# The_Extender_PCB.net
KiCad netlist of a schematic drawn in EAGLE
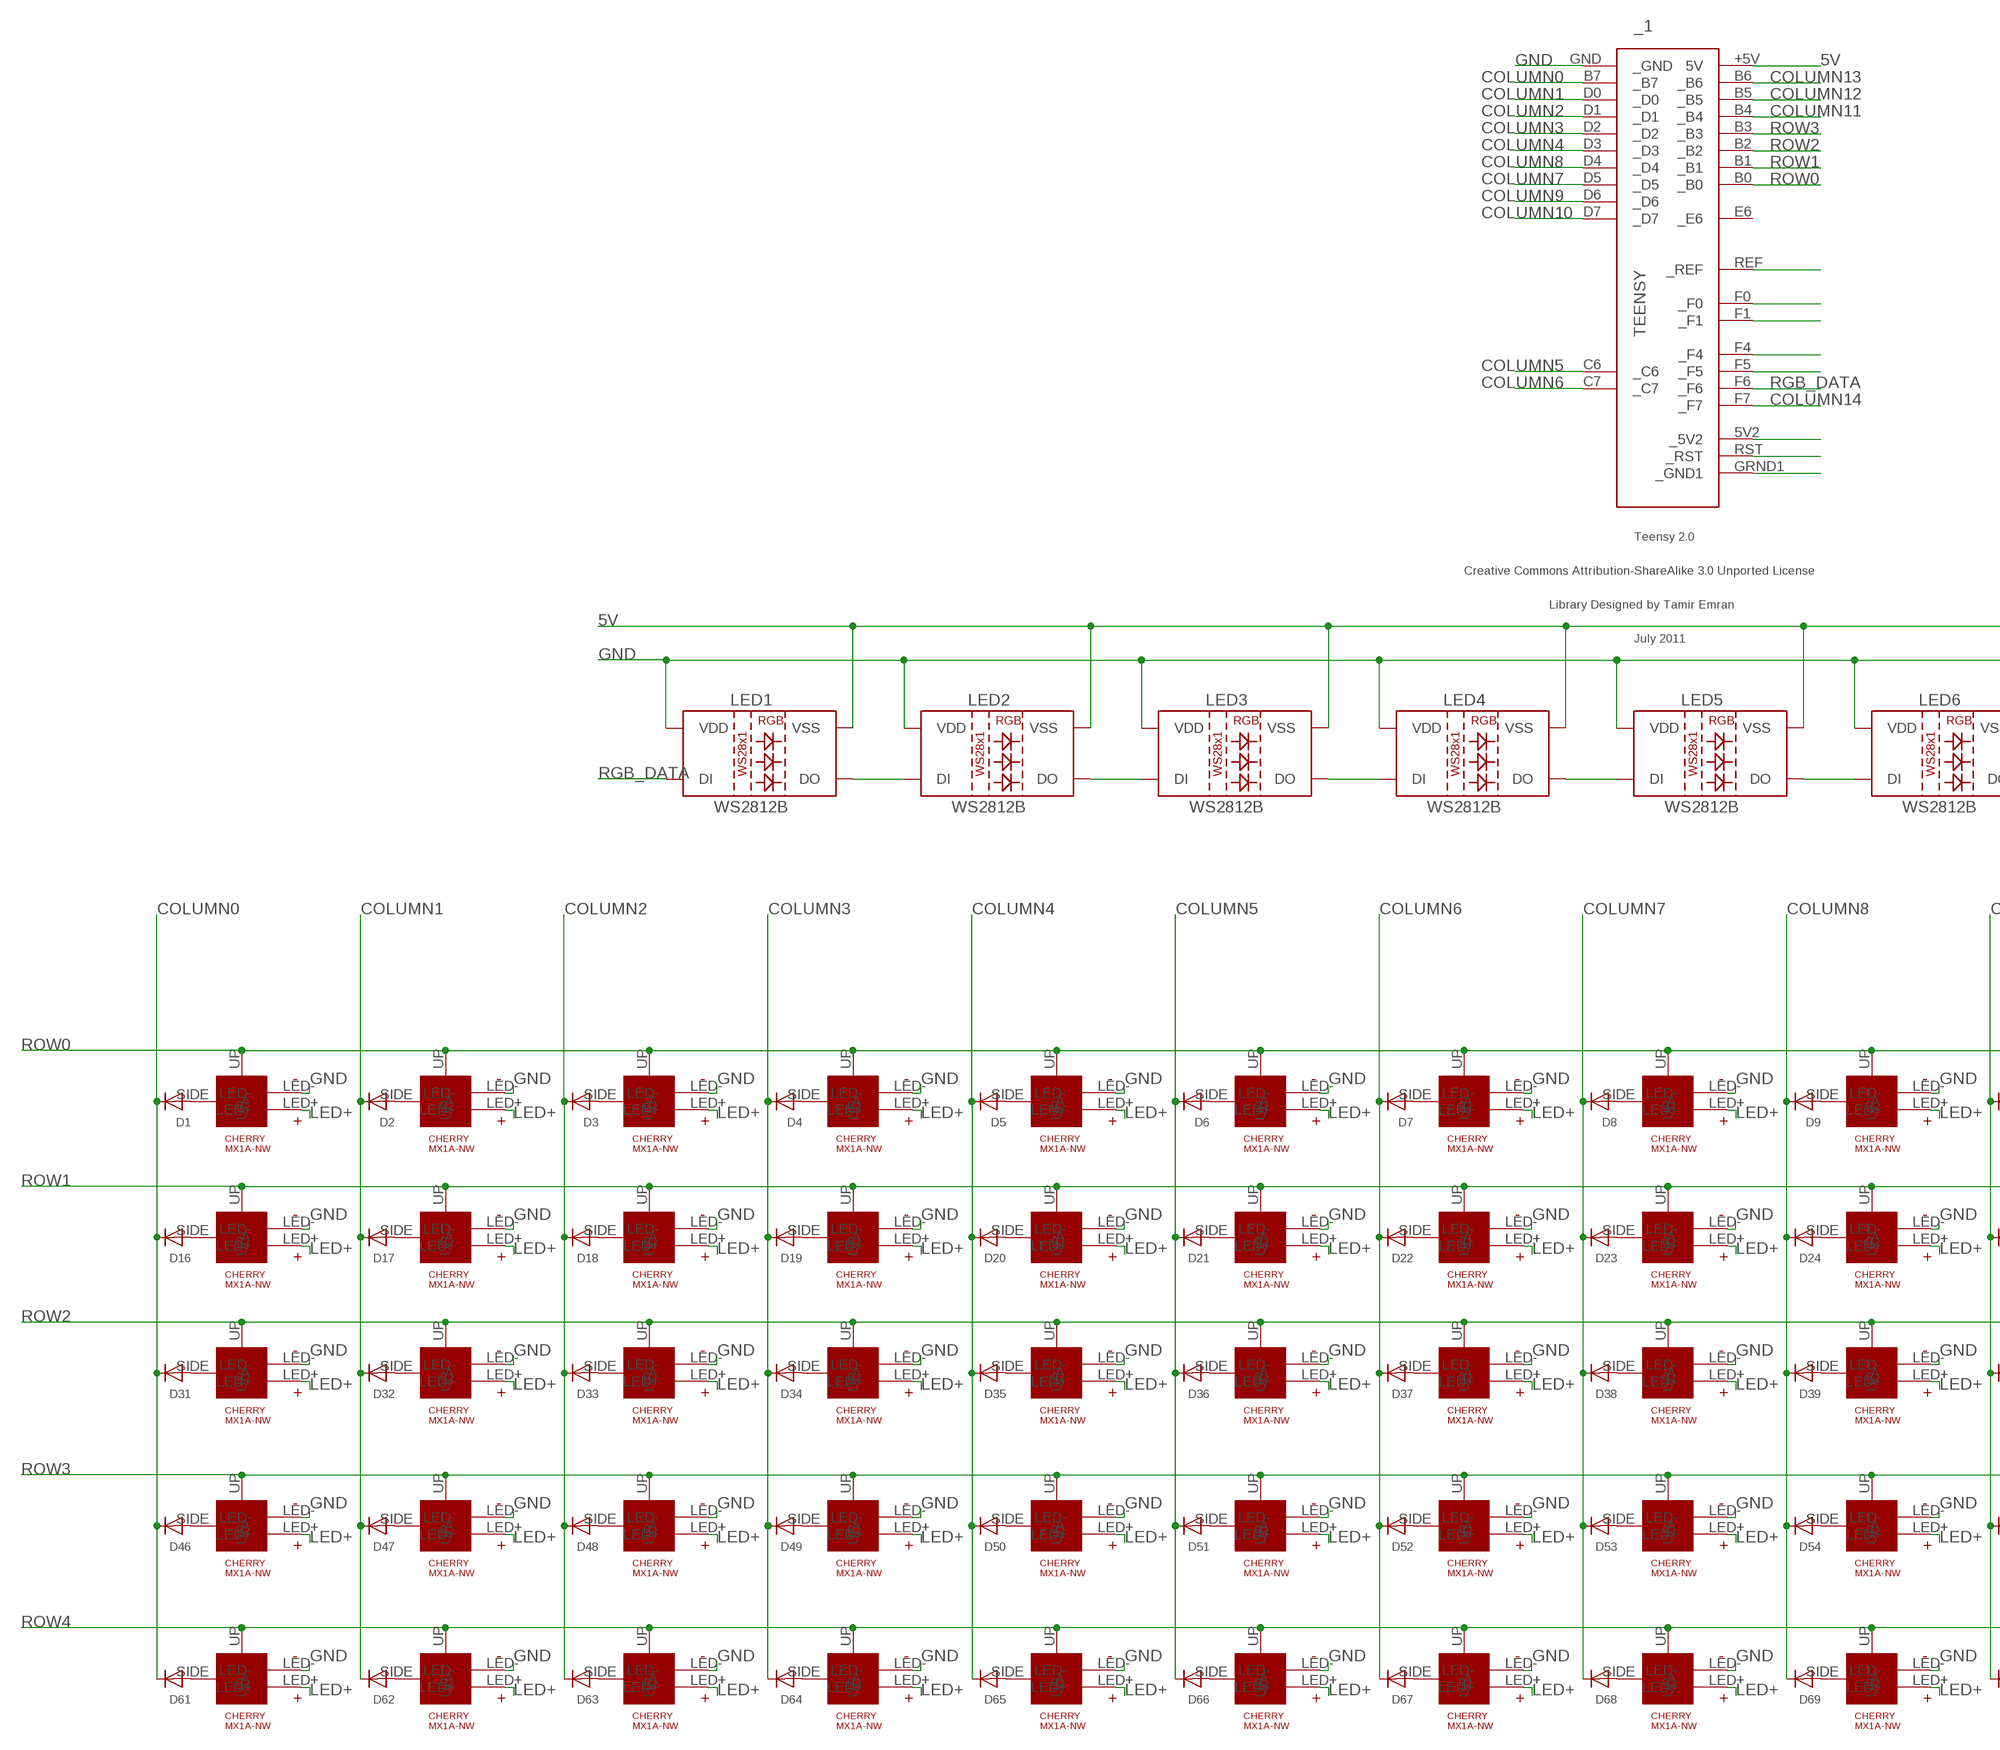
[diagram p0: schematic, sheet 1, part 1 of 2]
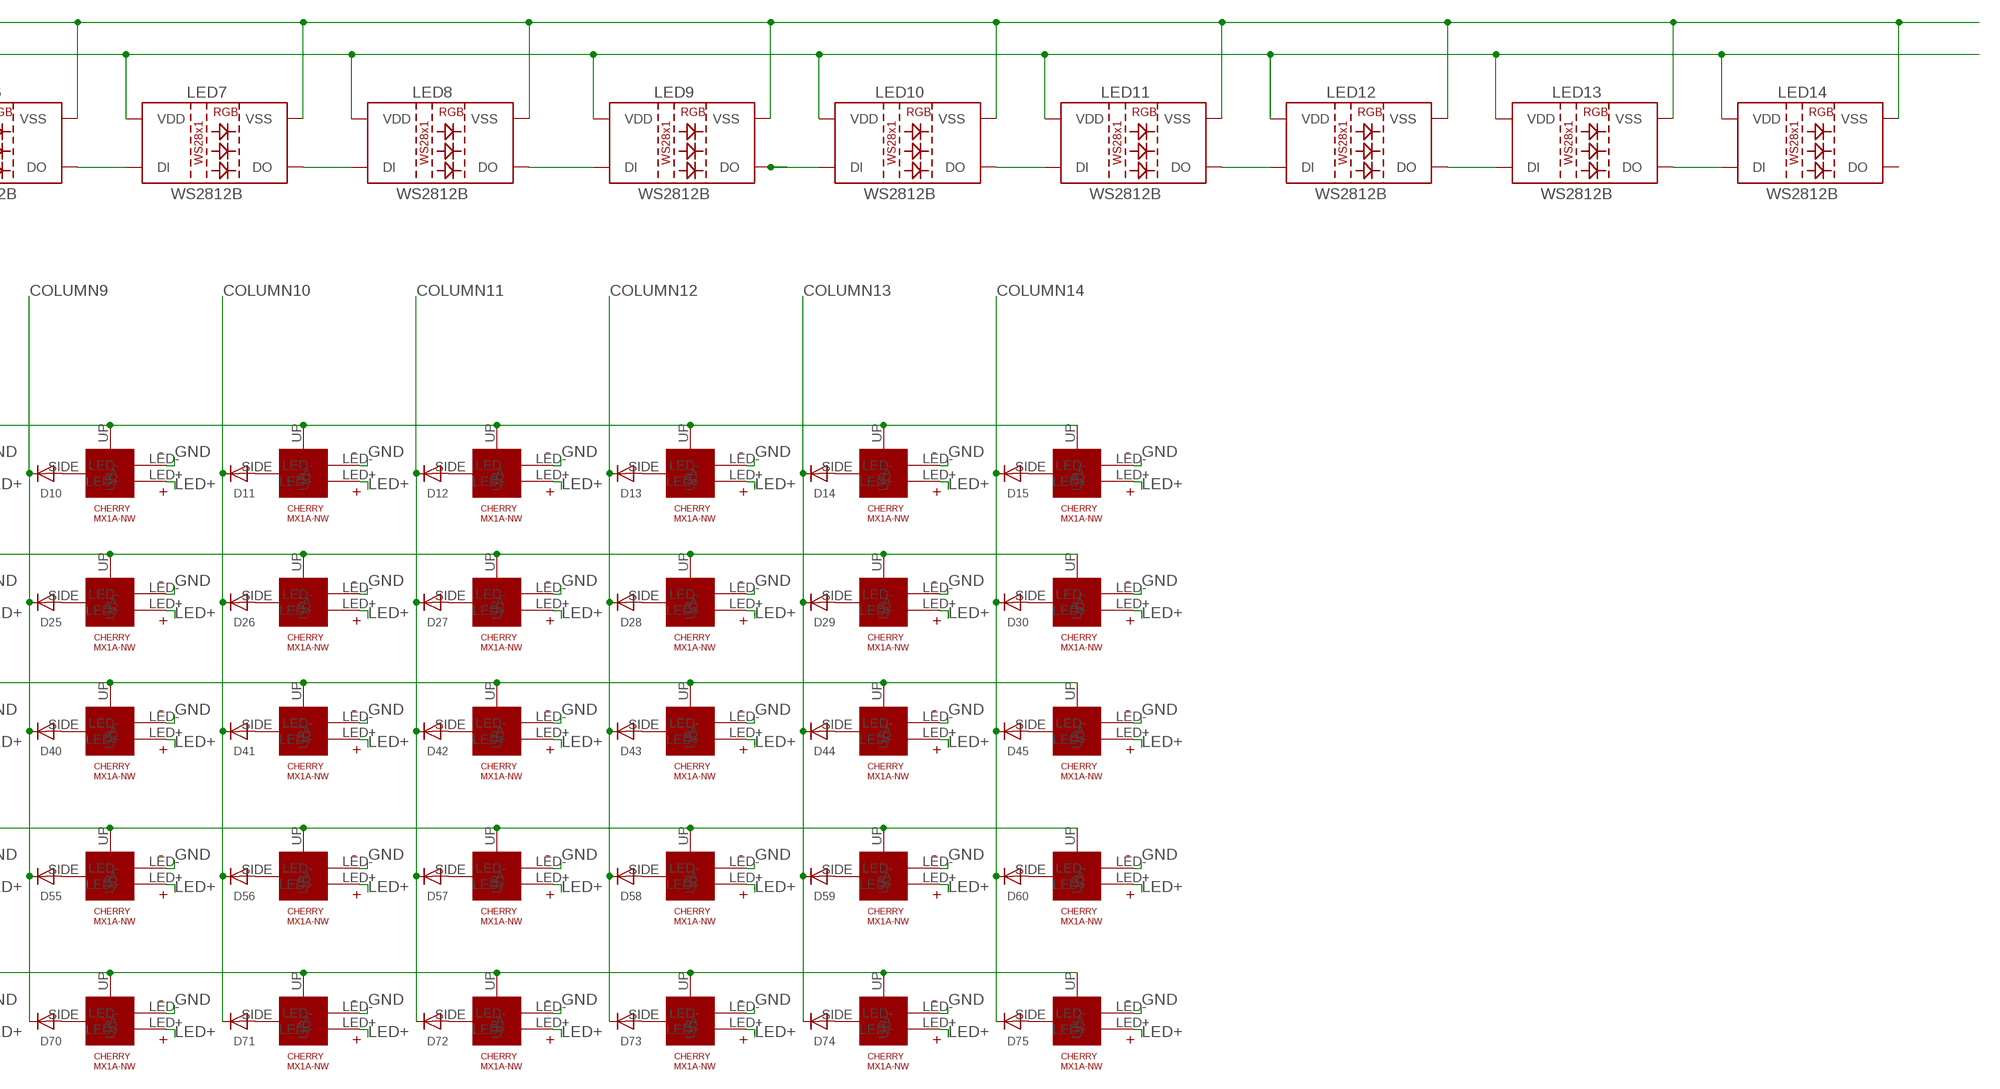
[diagram p1: schematic, sheet 1, part 2 of 2]

(export (version "E")
  (design (tool "Eeschema 10.0.6"))
  (components
    (comp (ref "D1")
      (value "DIODEDO-1N4148")
      (footprint "eagle-import:DO-1N4148")
      (libsource (lib "eagle-import") (part "DIODEDO-1N4148"))
    )
    (comp (ref "D2")
      (value "DIODEDO-1N4148")
      (footprint "eagle-import:DO-1N4148")
      (libsource (lib "eagle-import") (part "DIODEDO-1N4148"))
    )
    (comp (ref "D3")
      (value "DIODEDO-1N4148")
      (footprint "eagle-import:DO-1N4148")
      (libsource (lib "eagle-import") (part "DIODEDO-1N4148"))
    )
    (comp (ref "D4")
      (value "DIODEDO-1N4148")
      (footprint "eagle-import:DO-1N4148")
      (libsource (lib "eagle-import") (part "DIODEDO-1N4148"))
    )
    (comp (ref "D5")
      (value "DIODEDO-1N4148")
      (footprint "eagle-import:DO-1N4148")
      (libsource (lib "eagle-import") (part "DIODEDO-1N4148"))
    )
    (comp (ref "D6")
      (value "DIODEDO-1N4148")
      (footprint "eagle-import:DO-1N4148")
      (libsource (lib "eagle-import") (part "DIODEDO-1N4148"))
    )
    (comp (ref "D7")
      (value "DIODEDO-1N4148")
      (footprint "eagle-import:DO-1N4148")
      (libsource (lib "eagle-import") (part "DIODEDO-1N4148"))
    )
    (comp (ref "D8")
      (value "DIODEDO-1N4148")
      (footprint "eagle-import:DO-1N4148")
      (libsource (lib "eagle-import") (part "DIODEDO-1N4148"))
    )
    (comp (ref "D9")
      (value "DIODEDO-1N4148")
      (footprint "eagle-import:DO-1N4148")
      (libsource (lib "eagle-import") (part "DIODEDO-1N4148"))
    )
    (comp (ref "D10")
      (value "DIODEDO-1N4148")
      (footprint "eagle-import:DO-1N4148")
      (libsource (lib "eagle-import") (part "DIODEDO-1N4148"))
    )
    (comp (ref "D11")
      (value "DIODEDO-1N4148")
      (footprint "eagle-import:DO-1N4148")
      (libsource (lib "eagle-import") (part "DIODEDO-1N4148"))
    )
    (comp (ref "D12")
      (value "DIODEDO-1N4148")
      (footprint "eagle-import:DO-1N4148")
      (libsource (lib "eagle-import") (part "DIODEDO-1N4148"))
    )
    (comp (ref "D13")
      (value "DIODEDO-1N4148")
      (footprint "eagle-import:DO-1N4148")
      (libsource (lib "eagle-import") (part "DIODEDO-1N4148"))
    )
    (comp (ref "D14")
      (value "DIODEDO-1N4148")
      (footprint "eagle-import:DO-1N4148")
      (libsource (lib "eagle-import") (part "DIODEDO-1N4148"))
    )
    (comp (ref "D15")
      (value "DIODEDO-1N4148")
      (footprint "eagle-import:DO-1N4148")
      (libsource (lib "eagle-import") (part "DIODEDO-1N4148"))
    )
    (comp (ref "D16")
      (value "DIODEDO-1N4148")
      (footprint "eagle-import:DO-1N4148")
      (libsource (lib "eagle-import") (part "DIODEDO-1N4148"))
    )
    (comp (ref "D17")
      (value "DIODEDO-1N4148")
      (footprint "eagle-import:DO-1N4148")
      (libsource (lib "eagle-import") (part "DIODEDO-1N4148"))
    )
    (comp (ref "D18")
      (value "DIODEDO-1N4148")
      (footprint "eagle-import:DO-1N4148")
      (libsource (lib "eagle-import") (part "DIODEDO-1N4148"))
    )
    (comp (ref "D19")
      (value "DIODEDO-1N4148")
      (footprint "eagle-import:DO-1N4148")
      (libsource (lib "eagle-import") (part "DIODEDO-1N4148"))
    )
    (comp (ref "D20")
      (value "DIODEDO-1N4148")
      (footprint "eagle-import:DO-1N4148")
      (libsource (lib "eagle-import") (part "DIODEDO-1N4148"))
    )
    (comp (ref "D21")
      (value "DIODEDO-1N4148")
      (footprint "eagle-import:DO-1N4148")
      (libsource (lib "eagle-import") (part "DIODEDO-1N4148"))
    )
    (comp (ref "D22")
      (value "DIODEDO-1N4148")
      (footprint "eagle-import:DO-1N4148")
      (libsource (lib "eagle-import") (part "DIODEDO-1N4148"))
    )
    (comp (ref "D23")
      (value "DIODEDO-1N4148")
      (footprint "eagle-import:DO-1N4148")
      (libsource (lib "eagle-import") (part "DIODEDO-1N4148"))
    )
    (comp (ref "D24")
      (value "DIODEDO-1N4148")
      (footprint "eagle-import:DO-1N4148")
      (libsource (lib "eagle-import") (part "DIODEDO-1N4148"))
    )
    (comp (ref "D25")
      (value "DIODEDO-1N4148")
      (footprint "eagle-import:DO-1N4148")
      (libsource (lib "eagle-import") (part "DIODEDO-1N4148"))
    )
    (comp (ref "D26")
      (value "DIODEDO-1N4148")
      (footprint "eagle-import:DO-1N4148")
      (libsource (lib "eagle-import") (part "DIODEDO-1N4148"))
    )
    (comp (ref "D27")
      (value "DIODEDO-1N4148")
      (footprint "eagle-import:DO-1N4148")
      (libsource (lib "eagle-import") (part "DIODEDO-1N4148"))
    )
    (comp (ref "D28")
      (value "DIODEDO-1N4148")
      (footprint "eagle-import:DO-1N4148")
      (libsource (lib "eagle-import") (part "DIODEDO-1N4148"))
    )
    (comp (ref "D29")
      (value "DIODEDO-1N4148")
      (footprint "eagle-import:DO-1N4148")
      (libsource (lib "eagle-import") (part "DIODEDO-1N4148"))
    )
    (comp (ref "D30")
      (value "DIODEDO-1N4148")
      (footprint "eagle-import:DO-1N4148")
      (libsource (lib "eagle-import") (part "DIODEDO-1N4148"))
    )
    (comp (ref "D31")
      (value "DIODEDO-1N4148")
      (footprint "eagle-import:DO-1N4148")
      (libsource (lib "eagle-import") (part "DIODEDO-1N4148"))
    )
    (comp (ref "D32")
      (value "DIODEDO-1N4148")
      (footprint "eagle-import:DO-1N4148")
      (libsource (lib "eagle-import") (part "DIODEDO-1N4148"))
    )
    (comp (ref "D33")
      (value "DIODEDO-1N4148")
      (footprint "eagle-import:DO-1N4148")
      (libsource (lib "eagle-import") (part "DIODEDO-1N4148"))
    )
    (comp (ref "D34")
      (value "DIODEDO-1N4148")
      (footprint "eagle-import:DO-1N4148")
      (libsource (lib "eagle-import") (part "DIODEDO-1N4148"))
    )
    (comp (ref "D35")
      (value "DIODEDO-1N4148")
      (footprint "eagle-import:DO-1N4148")
      (libsource (lib "eagle-import") (part "DIODEDO-1N4148"))
    )
    (comp (ref "D36")
      (value "DIODEDO-1N4148")
      (footprint "eagle-import:DO-1N4148")
      (libsource (lib "eagle-import") (part "DIODEDO-1N4148"))
    )
    (comp (ref "D37")
      (value "DIODEDO-1N4148")
      (footprint "eagle-import:DO-1N4148")
      (libsource (lib "eagle-import") (part "DIODEDO-1N4148"))
    )
    (comp (ref "D38")
      (value "DIODEDO-1N4148")
      (footprint "eagle-import:DO-1N4148")
      (libsource (lib "eagle-import") (part "DIODEDO-1N4148"))
    )
    (comp (ref "D39")
      (value "DIODEDO-1N4148")
      (footprint "eagle-import:DO-1N4148")
      (libsource (lib "eagle-import") (part "DIODEDO-1N4148"))
    )
    (comp (ref "D40")
      (value "DIODEDO-1N4148")
      (footprint "eagle-import:DO-1N4148")
      (libsource (lib "eagle-import") (part "DIODEDO-1N4148"))
    )
    (comp (ref "D41")
      (value "DIODEDO-1N4148")
      (footprint "eagle-import:DO-1N4148")
      (libsource (lib "eagle-import") (part "DIODEDO-1N4148"))
    )
    (comp (ref "D42")
      (value "DIODEDO-1N4148")
      (footprint "eagle-import:DO-1N4148")
      (libsource (lib "eagle-import") (part "DIODEDO-1N4148"))
    )
    (comp (ref "D43")
      (value "DIODEDO-1N4148")
      (footprint "eagle-import:DO-1N4148")
      (libsource (lib "eagle-import") (part "DIODEDO-1N4148"))
    )
    (comp (ref "D44")
      (value "DIODEDO-1N4148")
      (footprint "eagle-import:DO-1N4148")
      (libsource (lib "eagle-import") (part "DIODEDO-1N4148"))
    )
    (comp (ref "D45")
      (value "DIODEDO-1N4148")
      (footprint "eagle-import:DO-1N4148")
      (libsource (lib "eagle-import") (part "DIODEDO-1N4148"))
    )
    (comp (ref "D46")
      (value "DIODEDO-1N4148")
      (footprint "eagle-import:DO-1N4148")
      (libsource (lib "eagle-import") (part "DIODEDO-1N4148"))
    )
    (comp (ref "D47")
      (value "DIODEDO-1N4148")
      (footprint "eagle-import:DO-1N4148")
      (libsource (lib "eagle-import") (part "DIODEDO-1N4148"))
    )
    (comp (ref "D48")
      (value "DIODEDO-1N4148")
      (footprint "eagle-import:DO-1N4148")
      (libsource (lib "eagle-import") (part "DIODEDO-1N4148"))
    )
    (comp (ref "D49")
      (value "DIODEDO-1N4148")
      (footprint "eagle-import:DO-1N4148")
      (libsource (lib "eagle-import") (part "DIODEDO-1N4148"))
    )
    (comp (ref "D50")
      (value "DIODEDO-1N4148")
      (footprint "eagle-import:DO-1N4148")
      (libsource (lib "eagle-import") (part "DIODEDO-1N4148"))
    )
    (comp (ref "D51")
      (value "DIODEDO-1N4148")
      (footprint "eagle-import:DO-1N4148")
      (libsource (lib "eagle-import") (part "DIODEDO-1N4148"))
    )
    (comp (ref "D52")
      (value "DIODEDO-1N4148")
      (footprint "eagle-import:DO-1N4148")
      (libsource (lib "eagle-import") (part "DIODEDO-1N4148"))
    )
    (comp (ref "D53")
      (value "DIODEDO-1N4148")
      (footprint "eagle-import:DO-1N4148")
      (libsource (lib "eagle-import") (part "DIODEDO-1N4148"))
    )
    (comp (ref "D54")
      (value "DIODEDO-1N4148")
      (footprint "eagle-import:DO-1N4148")
      (libsource (lib "eagle-import") (part "DIODEDO-1N4148"))
    )
    (comp (ref "D55")
      (value "DIODEDO-1N4148")
      (footprint "eagle-import:DO-1N4148")
      (libsource (lib "eagle-import") (part "DIODEDO-1N4148"))
    )
    (comp (ref "D56")
      (value "DIODEDO-1N4148")
      (footprint "eagle-import:DO-1N4148")
      (libsource (lib "eagle-import") (part "DIODEDO-1N4148"))
    )
    (comp (ref "D57")
      (value "DIODEDO-1N4148")
      (footprint "eagle-import:DO-1N4148")
      (libsource (lib "eagle-import") (part "DIODEDO-1N4148"))
    )
    (comp (ref "D58")
      (value "DIODEDO-1N4148")
      (footprint "eagle-import:DO-1N4148")
      (libsource (lib "eagle-import") (part "DIODEDO-1N4148"))
    )
    (comp (ref "D59")
      (value "DIODEDO-1N4148")
      (footprint "eagle-import:DO-1N4148")
      (libsource (lib "eagle-import") (part "DIODEDO-1N4148"))
    )
    (comp (ref "D60")
      (value "DIODEDO-1N4148")
      (footprint "eagle-import:DO-1N4148")
      (libsource (lib "eagle-import") (part "DIODEDO-1N4148"))
    )
    (comp (ref "D61")
      (value "DIODEDO-1N4148")
      (footprint "eagle-import:DO-1N4148")
      (libsource (lib "eagle-import") (part "DIODEDO-1N4148"))
    )
    (comp (ref "D62")
      (value "DIODEDO-1N4148")
      (footprint "eagle-import:DO-1N4148")
      (libsource (lib "eagle-import") (part "DIODEDO-1N4148"))
    )
    (comp (ref "D63")
      (value "DIODEDO-1N4148")
      (footprint "eagle-import:DO-1N4148")
      (libsource (lib "eagle-import") (part "DIODEDO-1N4148"))
    )
    (comp (ref "D64")
      (value "DIODEDO-1N4148")
      (footprint "eagle-import:DO-1N4148")
      (libsource (lib "eagle-import") (part "DIODEDO-1N4148"))
    )
    (comp (ref "D65")
      (value "DIODEDO-1N4148")
      (footprint "eagle-import:DO-1N4148")
      (libsource (lib "eagle-import") (part "DIODEDO-1N4148"))
    )
    (comp (ref "D66")
      (value "DIODEDO-1N4148")
      (footprint "eagle-import:DO-1N4148")
      (libsource (lib "eagle-import") (part "DIODEDO-1N4148"))
    )
    (comp (ref "D67")
      (value "DIODEDO-1N4148")
      (footprint "eagle-import:DO-1N4148")
      (libsource (lib "eagle-import") (part "DIODEDO-1N4148"))
    )
    (comp (ref "D68")
      (value "DIODEDO-1N4148")
      (footprint "eagle-import:DO-1N4148")
      (libsource (lib "eagle-import") (part "DIODEDO-1N4148"))
    )
    (comp (ref "D69")
      (value "DIODEDO-1N4148")
      (footprint "eagle-import:DO-1N4148")
      (libsource (lib "eagle-import") (part "DIODEDO-1N4148"))
    )
    (comp (ref "D70")
      (value "DIODEDO-1N4148")
      (footprint "eagle-import:DO-1N4148")
      (libsource (lib "eagle-import") (part "DIODEDO-1N4148"))
    )
    (comp (ref "D71")
      (value "DIODEDO-1N4148")
      (footprint "eagle-import:DO-1N4148")
      (libsource (lib "eagle-import") (part "DIODEDO-1N4148"))
    )
    (comp (ref "D72")
      (value "DIODEDO-1N4148")
      (footprint "eagle-import:DO-1N4148")
      (libsource (lib "eagle-import") (part "DIODEDO-1N4148"))
    )
    (comp (ref "D73")
      (value "DIODEDO-1N4148")
      (footprint "eagle-import:DO-1N4148")
      (libsource (lib "eagle-import") (part "DIODEDO-1N4148"))
    )
    (comp (ref "D74")
      (value "DIODEDO-1N4148")
      (footprint "eagle-import:DO-1N4148")
      (libsource (lib "eagle-import") (part "DIODEDO-1N4148"))
    )
    (comp (ref "D75")
      (value "DIODEDO-1N4148")
      (footprint "eagle-import:DO-1N4148")
      (libsource (lib "eagle-import") (part "DIODEDO-1N4148"))
    )
    (comp (ref "LED1")
      (value "WS2812B")
      (footprint "eagle-import:WS2812B")
      (libsource (lib "eagle-import") (part "WS2812B"))
    )
    (comp (ref "LED2")
      (value "WS2812B")
      (footprint "eagle-import:WS2812B")
      (libsource (lib "eagle-import") (part "WS2812B"))
    )
    (comp (ref "LED3")
      (value "WS2812B")
      (footprint "eagle-import:WS2812B")
      (libsource (lib "eagle-import") (part "WS2812B"))
    )
    (comp (ref "LED4")
      (value "WS2812B")
      (footprint "eagle-import:WS2812B")
      (libsource (lib "eagle-import") (part "WS2812B"))
    )
    (comp (ref "LED5")
      (value "WS2812B")
      (footprint "eagle-import:WS2812B")
      (libsource (lib "eagle-import") (part "WS2812B"))
    )
    (comp (ref "LED6")
      (value "WS2812B")
      (footprint "eagle-import:WS2812B")
      (libsource (lib "eagle-import") (part "WS2812B"))
    )
    (comp (ref "LED7")
      (value "WS2812B")
      (footprint "eagle-import:WS2812B")
      (libsource (lib "eagle-import") (part "WS2812B"))
    )
    (comp (ref "LED8")
      (value "WS2812B")
      (footprint "eagle-import:WS2812B")
      (libsource (lib "eagle-import") (part "WS2812B"))
    )
    (comp (ref "LED9")
      (value "WS2812B")
      (footprint "eagle-import:WS2812B")
      (libsource (lib "eagle-import") (part "WS2812B"))
    )
    (comp (ref "LED10")
      (value "WS2812B")
      (footprint "eagle-import:WS2812B")
      (libsource (lib "eagle-import") (part "WS2812B"))
    )
    (comp (ref "LED11")
      (value "WS2812B")
      (footprint "eagle-import:WS2812B")
      (libsource (lib "eagle-import") (part "WS2812B"))
    )
    (comp (ref "LED12")
      (value "WS2812B")
      (footprint "eagle-import:WS2812B")
      (libsource (lib "eagle-import") (part "WS2812B"))
    )
    (comp (ref "LED13")
      (value "WS2812B")
      (footprint "eagle-import:WS2812B")
      (libsource (lib "eagle-import") (part "WS2812B"))
    )
    (comp (ref "LED14")
      (value "WS2812B")
      (footprint "eagle-import:WS2812B")
      (libsource (lib "eagle-import") (part "WS2812B"))
    )
    (comp (ref "U$1")
      (value "CHERRY-MX1A-E1NW-LED")
      (footprint "eagle-import:CHERRYMX-NN-LED")
      (libsource (lib "eagle-import") (part "CHERRY-MX1A-E1NW-LED"))
    )
    (comp (ref "U$2")
      (value "CHERRY-MX1A-E1NW-LED")
      (footprint "eagle-import:CHERRYMX-NN-LED")
      (libsource (lib "eagle-import") (part "CHERRY-MX1A-E1NW-LED"))
    )
    (comp (ref "U$3")
      (value "CHERRY-MX1A-E1NW-LED")
      (footprint "eagle-import:CHERRYMX-NN-LED")
      (libsource (lib "eagle-import") (part "CHERRY-MX1A-E1NW-LED"))
    )
    (comp (ref "U$4")
      (value "CHERRY-MX1A-E1NW-LED")
      (footprint "eagle-import:CHERRYMX-NN-LED")
      (libsource (lib "eagle-import") (part "CHERRY-MX1A-E1NW-LED"))
    )
    (comp (ref "U$5")
      (value "CHERRY-MX1A-E1NW-LED")
      (footprint "eagle-import:CHERRYMX-NN-LED")
      (libsource (lib "eagle-import") (part "CHERRY-MX1A-E1NW-LED"))
    )
    (comp (ref "U$6")
      (value "CHERRY-MX1A-E1NW-LED")
      (footprint "eagle-import:CHERRYMX-NN-LED")
      (libsource (lib "eagle-import") (part "CHERRY-MX1A-E1NW-LED"))
    )
    (comp (ref "U$7")
      (value "CHERRY-MX1A-E1NW-LED")
      (footprint "eagle-import:CHERRYMX-NN-LED")
      (libsource (lib "eagle-import") (part "CHERRY-MX1A-E1NW-LED"))
    )
    (comp (ref "U$8")
      (value "CHERRY-MX1A-E1NW-LED")
      (footprint "eagle-import:CHERRYMX-NN-LED")
      (libsource (lib "eagle-import") (part "CHERRY-MX1A-E1NW-LED"))
    )
    (comp (ref "U$9")
      (value "CHERRY-MX1A-E1NW-LED")
      (footprint "eagle-import:CHERRYMX-NN-LED")
      (libsource (lib "eagle-import") (part "CHERRY-MX1A-E1NW-LED"))
    )
    (comp (ref "U$10")
      (value "CHERRY-MX1A-E1NW-LED")
      (footprint "eagle-import:CHERRYMX-NN-LED")
      (libsource (lib "eagle-import") (part "CHERRY-MX1A-E1NW-LED"))
    )
    (comp (ref "U$11")
      (value "CHERRY-MX1A-E1NW-LED")
      (footprint "eagle-import:CHERRYMX-NN-LED")
      (libsource (lib "eagle-import") (part "CHERRY-MX1A-E1NW-LED"))
    )
    (comp (ref "U$12")
      (value "CHERRY-MX1A-E1NW-LED")
      (footprint "eagle-import:CHERRYMX-NN-LED")
      (libsource (lib "eagle-import") (part "CHERRY-MX1A-E1NW-LED"))
    )
    (comp (ref "U$13")
      (value "CHERRY-MX1A-E1NW-LED")
      (footprint "eagle-import:CHERRYMX-NN-LED")
      (libsource (lib "eagle-import") (part "CHERRY-MX1A-E1NW-LED"))
    )
    (comp (ref "U$14")
      (value "CHERRY-MX1A-E1NW-LED")
      (footprint "eagle-import:CHERRYMX-NN-LED")
      (libsource (lib "eagle-import") (part "CHERRY-MX1A-E1NW-LED"))
    )
    (comp (ref "U$15")
      (value "CHERRY-MX1A-E1NW-LED")
      (footprint "eagle-import:CHERRYMX-NN-LED")
      (libsource (lib "eagle-import") (part "CHERRY-MX1A-E1NW-LED"))
    )
    (comp (ref "U$16")
      (value "CHERRY-MX1A-E1NW-LED")
      (footprint "eagle-import:CHERRYMX-NN-LED")
      (libsource (lib "eagle-import") (part "CHERRY-MX1A-E1NW-LED"))
    )
    (comp (ref "U$17")
      (value "CHERRY-MX1A-E1NW-LED")
      (footprint "eagle-import:CHERRYMX-NN-LED")
      (libsource (lib "eagle-import") (part "CHERRY-MX1A-E1NW-LED"))
    )
    (comp (ref "U$18")
      (value "CHERRY-MX1A-E1NW-LED")
      (footprint "eagle-import:CHERRYMX-NN-LED")
      (libsource (lib "eagle-import") (part "CHERRY-MX1A-E1NW-LED"))
    )
    (comp (ref "U$19")
      (value "CHERRY-MX1A-E1NW-LED")
      (footprint "eagle-import:CHERRYMX-NN-LED")
      (libsource (lib "eagle-import") (part "CHERRY-MX1A-E1NW-LED"))
    )
    (comp (ref "U$20")
      (value "CHERRY-MX1A-E1NW-LED")
      (footprint "eagle-import:CHERRYMX-NN-LED")
      (libsource (lib "eagle-import") (part "CHERRY-MX1A-E1NW-LED"))
    )
    (comp (ref "U$21")
      (value "CHERRY-MX1A-E1NW-LED")
      (footprint "eagle-import:CHERRYMX-NN-LED")
      (libsource (lib "eagle-import") (part "CHERRY-MX1A-E1NW-LED"))
    )
    (comp (ref "U$22")
      (value "CHERRY-MX1A-E1NW-LED")
      (footprint "eagle-import:CHERRYMX-NN-LED")
      (libsource (lib "eagle-import") (part "CHERRY-MX1A-E1NW-LED"))
    )
    (comp (ref "U$23")
      (value "CHERRY-MX1A-E1NW-LED")
      (footprint "eagle-import:CHERRYMX-NN-LED")
      (libsource (lib "eagle-import") (part "CHERRY-MX1A-E1NW-LED"))
    )
    (comp (ref "U$24")
      (value "CHERRY-MX1A-E1NW-LED")
      (footprint "eagle-import:CHERRYMX-NN-LED")
      (libsource (lib "eagle-import") (part "CHERRY-MX1A-E1NW-LED"))
    )
    (comp (ref "U$25")
      (value "CHERRY-MX1A-E1NW-LED")
      (footprint "eagle-import:CHERRYMX-NN-LED")
      (libsource (lib "eagle-import") (part "CHERRY-MX1A-E1NW-LED"))
    )
    (comp (ref "U$26")
      (value "CHERRY-MX1A-E1NW-LED")
      (footprint "eagle-import:CHERRYMX-NN-LED")
      (libsource (lib "eagle-import") (part "CHERRY-MX1A-E1NW-LED"))
    )
    (comp (ref "U$27")
      (value "CHERRY-MX1A-E1NW-LED")
      (footprint "eagle-import:CHERRYMX-NN-LED")
      (libsource (lib "eagle-import") (part "CHERRY-MX1A-E1NW-LED"))
    )
    (comp (ref "U$28")
      (value "CHERRY-MX1A-E1NW-LED")
      (footprint "eagle-import:CHERRYMX-NN-LED")
      (libsource (lib "eagle-import") (part "CHERRY-MX1A-E1NW-LED"))
    )
    (comp (ref "U$29")
      (value "CHERRY-MX1A-E1NW-LED")
      (footprint "eagle-import:CHERRYMX-NN-LED")
      (libsource (lib "eagle-import") (part "CHERRY-MX1A-E1NW-LED"))
    )
    (comp (ref "U$30")
      (value "CHERRY-MX1A-E1NW-LED")
      (footprint "eagle-import:CHERRYMX-NN-LED")
      (libsource (lib "eagle-import") (part "CHERRY-MX1A-E1NW-LED"))
    )
    (comp (ref "U$31")
      (value "CHERRY-MX1A-E1NW-LED")
      (footprint "eagle-import:CHERRYMX-NN-LED")
      (libsource (lib "eagle-import") (part "CHERRY-MX1A-E1NW-LED"))
    )
    (comp (ref "U$32")
      (value "CHERRY-MX1A-E1NW-LED")
      (footprint "eagle-import:CHERRYMX-NN-LED")
      (libsource (lib "eagle-import") (part "CHERRY-MX1A-E1NW-LED"))
    )
    (comp (ref "U$33")
      (value "CHERRY-MX1A-E1NW-LED")
      (footprint "eagle-import:CHERRYMX-NN-LED")
      (libsource (lib "eagle-import") (part "CHERRY-MX1A-E1NW-LED"))
    )
    (comp (ref "U$34")
      (value "CHERRY-MX1A-E1NW-LED")
      (footprint "eagle-import:CHERRYMX-NN-LED")
      (libsource (lib "eagle-import") (part "CHERRY-MX1A-E1NW-LED"))
    )
    (comp (ref "U$35")
      (value "CHERRY-MX1A-E1NW-LED")
      (footprint "eagle-import:CHERRYMX-NN-LED")
      (libsource (lib "eagle-import") (part "CHERRY-MX1A-E1NW-LED"))
    )
    (comp (ref "U$36")
      (value "CHERRY-MX1A-E1NW-LED")
      (footprint "eagle-import:CHERRYMX-NN-LED")
      (libsource (lib "eagle-import") (part "CHERRY-MX1A-E1NW-LED"))
    )
    (comp (ref "U$37")
      (value "CHERRY-MX1A-E1NW-LED")
      (footprint "eagle-import:CHERRYMX-NN-LED")
      (libsource (lib "eagle-import") (part "CHERRY-MX1A-E1NW-LED"))
    )
    (comp (ref "U$38")
      (value "CHERRY-MX1A-E1NW-LED")
      (footprint "eagle-import:CHERRYMX-NN-LED")
      (libsource (lib "eagle-import") (part "CHERRY-MX1A-E1NW-LED"))
    )
    (comp (ref "U$39")
      (value "CHERRY-MX1A-E1NW-LED")
      (footprint "eagle-import:CHERRYMX-NN-LED")
      (libsource (lib "eagle-import") (part "CHERRY-MX1A-E1NW-LED"))
    )
    (comp (ref "U$40")
      (value "CHERRY-MX1A-E1NW-LED")
      (footprint "eagle-import:CHERRYMX-NN-LED")
      (libsource (lib "eagle-import") (part "CHERRY-MX1A-E1NW-LED"))
    )
    (comp (ref "U$41")
      (value "CHERRY-MX1A-E1NW-LED")
      (footprint "eagle-import:CHERRYMX-NN-LED")
      (libsource (lib "eagle-import") (part "CHERRY-MX1A-E1NW-LED"))
    )
    (comp (ref "U$42")
      (value "CHERRY-MX1A-E1NW-LED")
      (footprint "eagle-import:CHERRYMX-NN-LED")
      (libsource (lib "eagle-import") (part "CHERRY-MX1A-E1NW-LED"))
    )
    (comp (ref "U$43")
      (value "CHERRY-MX1A-E1NW-LED")
      (footprint "eagle-import:CHERRYMX-NN-LED")
      (libsource (lib "eagle-import") (part "CHERRY-MX1A-E1NW-LED"))
    )
    (comp (ref "U$44")
      (value "CHERRY-MX1A-E1NW-LED")
      (footprint "eagle-import:CHERRYMX-NN-LED")
      (libsource (lib "eagle-import") (part "CHERRY-MX1A-E1NW-LED"))
    )
    (comp (ref "U$45")
      (value "CHERRY-MX1A-E1NW-LED")
      (footprint "eagle-import:CHERRYMX-NN-LED")
      (libsource (lib "eagle-import") (part "CHERRY-MX1A-E1NW-LED"))
    )
    (comp (ref "U$46")
      (value "CHERRY-MX1A-E1NW-LED")
      (footprint "eagle-import:CHERRYMX-NN-LED")
      (libsource (lib "eagle-import") (part "CHERRY-MX1A-E1NW-LED"))
    )
    (comp (ref "U$47")
      (value "CHERRY-MX1A-E1NW-LED")
      (footprint "eagle-import:CHERRYMX-NN-LED")
      (libsource (lib "eagle-import") (part "CHERRY-MX1A-E1NW-LED"))
    )
    (comp (ref "U$48")
      (value "CHERRY-MX1A-E1NW-LED")
      (footprint "eagle-import:CHERRYMX-NN-LED")
      (libsource (lib "eagle-import") (part "CHERRY-MX1A-E1NW-LED"))
    )
    (comp (ref "U$49")
      (value "CHERRY-MX1A-E1NW-LED")
      (footprint "eagle-import:CHERRYMX-NN-LED")
      (libsource (lib "eagle-import") (part "CHERRY-MX1A-E1NW-LED"))
    )
    (comp (ref "U$50")
      (value "CHERRY-MX1A-E1NW-LED")
      (footprint "eagle-import:CHERRYMX-NN-LED")
      (libsource (lib "eagle-import") (part "CHERRY-MX1A-E1NW-LED"))
    )
    (comp (ref "U$51")
      (value "CHERRY-MX1A-E1NW-LED")
      (footprint "eagle-import:CHERRYMX-NN-LED")
      (libsource (lib "eagle-import") (part "CHERRY-MX1A-E1NW-LED"))
    )
    (comp (ref "U$52")
      (value "CHERRY-MX1A-E1NW-LED")
      (footprint "eagle-import:CHERRYMX-NN-LED")
      (libsource (lib "eagle-import") (part "CHERRY-MX1A-E1NW-LED"))
    )
    (comp (ref "U$53")
      (value "CHERRY-MX1A-E1NW-LED")
      (footprint "eagle-import:CHERRYMX-NN-LED")
      (libsource (lib "eagle-import") (part "CHERRY-MX1A-E1NW-LED"))
    )
    (comp (ref "U$54")
      (value "CHERRY-MX1A-E1NW-LED")
      (footprint "eagle-import:CHERRYMX-NN-LED")
      (libsource (lib "eagle-import") (part "CHERRY-MX1A-E1NW-LED"))
    )
    (comp (ref "U$55")
      (value "CHERRY-MX1A-E1NW-LED")
      (footprint "eagle-import:CHERRYMX-NN-LED")
      (libsource (lib "eagle-import") (part "CHERRY-MX1A-E1NW-LED"))
    )
    (comp (ref "U$56")
      (value "CHERRY-MX1A-E1NW-LED")
      (footprint "eagle-import:CHERRYMX-NN-LED")
      (libsource (lib "eagle-import") (part "CHERRY-MX1A-E1NW-LED"))
    )
    (comp (ref "U$57")
      (value "CHERRY-MX1A-E1NW-LED")
      (footprint "eagle-import:CHERRYMX-NN-LED")
      (libsource (lib "eagle-import") (part "CHERRY-MX1A-E1NW-LED"))
    )
    (comp (ref "U$58")
      (value "CHERRY-MX1A-E1NW-LED")
      (footprint "eagle-import:CHERRYMX-NN-LED")
      (libsource (lib "eagle-import") (part "CHERRY-MX1A-E1NW-LED"))
    )
    (comp (ref "U$59")
      (value "CHERRY-MX1A-E1NW-LED")
      (footprint "eagle-import:CHERRYMX-NN-LED")
      (libsource (lib "eagle-import") (part "CHERRY-MX1A-E1NW-LED"))
    )
    (comp (ref "U$60")
      (value "CHERRY-MX1A-E1NW-LED")
      (footprint "eagle-import:CHERRYMX-NN-LED")
      (libsource (lib "eagle-import") (part "CHERRY-MX1A-E1NW-LED"))
    )
    (comp (ref "U$61")
      (value "CHERRY-MX1A-E1NW-LED")
      (footprint "eagle-import:CHERRYMX-NN-LED")
      (libsource (lib "eagle-import") (part "CHERRY-MX1A-E1NW-LED"))
    )
    (comp (ref "U$62")
      (value "CHERRY-MX1A-E1NW-LED")
      (footprint "eagle-import:CHERRYMX-NN-LED")
      (libsource (lib "eagle-import") (part "CHERRY-MX1A-E1NW-LED"))
    )
    (comp (ref "U$63")
      (value "CHERRY-MX1A-E1NW-LED")
      (footprint "eagle-import:CHERRYMX-NN-LED")
      (libsource (lib "eagle-import") (part "CHERRY-MX1A-E1NW-LED"))
    )
    (comp (ref "U$64")
      (value "CHERRY-MX1A-E1NW-LED")
      (footprint "eagle-import:CHERRYMX-NN-LED")
      (libsource (lib "eagle-import") (part "CHERRY-MX1A-E1NW-LED"))
    )
    (comp (ref "U$65")
      (value "CHERRY-MX1A-E1NW-LED")
      (footprint "eagle-import:CHERRYMX-NN-LED")
      (libsource (lib "eagle-import") (part "CHERRY-MX1A-E1NW-LED"))
    )
    (comp (ref "U$66")
      (value "CHERRY-MX1A-E1NW-LED")
      (footprint "eagle-import:CHERRYMX-NN-LED")
      (libsource (lib "eagle-import") (part "CHERRY-MX1A-E1NW-LED"))
    )
    (comp (ref "U$67")
      (value "CHERRY-MX1A-E1NW-LED")
      (footprint "eagle-import:CHERRYMX-NN-LED")
      (libsource (lib "eagle-import") (part "CHERRY-MX1A-E1NW-LED"))
    )
    (comp (ref "U$68")
      (value "CHERRY-MX1A-E1NW-LED")
      (footprint "eagle-import:CHERRYMX-NN-LED")
      (libsource (lib "eagle-import") (part "CHERRY-MX1A-E1NW-LED"))
    )
    (comp (ref "U$69")
      (value "CHERRY-MX1A-E1NW-LED")
      (footprint "eagle-import:CHERRYMX-NN-LED")
      (libsource (lib "eagle-import") (part "CHERRY-MX1A-E1NW-LED"))
    )
    (comp (ref "U$70")
      (value "CHERRY-MX1A-E1NW-LED")
      (footprint "eagle-import:CHERRYMX-NN-LED")
      (libsource (lib "eagle-import") (part "CHERRY-MX1A-E1NW-LED"))
    )
    (comp (ref "U$71")
      (value "CHERRY-MX1A-E1NW-LED")
      (footprint "eagle-import:CHERRYMX-NN-LED")
      (libsource (lib "eagle-import") (part "CHERRY-MX1A-E1NW-LED"))
    )
    (comp (ref "U$72")
      (value "CHERRY-MX1A-E1NW-LED")
      (footprint "eagle-import:CHERRYMX-NN-LED")
      (libsource (lib "eagle-import") (part "CHERRY-MX1A-E1NW-LED"))
    )
    (comp (ref "U$73")
      (value "CHERRY-MX1A-E1NW-LED")
      (footprint "eagle-import:CHERRYMX-NN-LED")
      (libsource (lib "eagle-import") (part "CHERRY-MX1A-E1NW-LED"))
    )
    (comp (ref "U$74")
      (value "CHERRY-MX1A-E1NW-LED")
      (footprint "eagle-import:CHERRYMX-NN-LED")
      (libsource (lib "eagle-import") (part "CHERRY-MX1A-E1NW-LED"))
    )
    (comp (ref "U$75")
      (value "CHERRY-MX1A-E1NW-LED")
      (footprint "eagle-import:CHERRYMX-NN-LED")
      (libsource (lib "eagle-import") (part "CHERRY-MX1A-E1NW-LED"))
    )
    (comp (ref "_1")
      (value "TEENSY")
      (footprint "eagle-import:TEENSY")
      (libsource (lib "eagle-import") (part "TEENSY"))
    )
  )
  (nets
    (net (code "1") (name "/5V") (class "Default")
      (node (ref "LED1") (pin "3") (pinfunction "VSS_3") (pintype "bidirectional"))
      (node (ref "LED10") (pin "3") (pinfunction "VSS_3") (pintype "bidirectional"))
      (node (ref "LED11") (pin "3") (pinfunction "VSS_3") (pintype "bidirectional"))
      (node (ref "LED12") (pin "3") (pinfunction "VSS_3") (pintype "bidirectional"))
      (node (ref "LED13") (pin "3") (pinfunction "VSS_3") (pintype "bidirectional"))
      (node (ref "LED14") (pin "3") (pinfunction "VSS_3") (pintype "bidirectional"))
      (node (ref "LED2") (pin "3") (pinfunction "VSS_3") (pintype "bidirectional"))
      (node (ref "LED3") (pin "3") (pinfunction "VSS_3") (pintype "bidirectional"))
      (node (ref "LED4") (pin "3") (pinfunction "VSS_3") (pintype "bidirectional"))
      (node (ref "LED5") (pin "3") (pinfunction "VSS_3") (pintype "bidirectional"))
      (node (ref "LED6") (pin "3") (pinfunction "VSS_3") (pintype "bidirectional"))
      (node (ref "LED7") (pin "3") (pinfunction "VSS_3") (pintype "bidirectional"))
      (node (ref "LED8") (pin "3") (pinfunction "VSS_3") (pintype "bidirectional"))
      (node (ref "LED9") (pin "3") (pinfunction "VSS_3") (pintype "bidirectional"))
      (node (ref "_1") (pin "+5V") (pinfunction "5V_+5V") (pintype "bidirectional"))
    )
    (net (code "2") (name "/COLUMN0") (class "Default")
      (node (ref "D1") (pin "C") (pinfunction "C_C") (pintype "passive"))
      (node (ref "D16") (pin "C") (pinfunction "C_C") (pintype "passive"))
      (node (ref "D31") (pin "C") (pinfunction "C_C") (pintype "passive"))
      (node (ref "D46") (pin "C") (pinfunction "C_C") (pintype "passive"))
      (node (ref "D61") (pin "C") (pinfunction "C_C") (pintype "passive"))
      (node (ref "_1") (pin "B7") (pinfunction "_B7_B7") (pintype "bidirectional"))
    )
    (net (code "3") (name "/COLUMN1") (class "Default")
      (node (ref "D17") (pin "C") (pinfunction "C_C") (pintype "passive"))
      (node (ref "D2") (pin "C") (pinfunction "C_C") (pintype "passive"))
      (node (ref "D32") (pin "C") (pinfunction "C_C") (pintype "passive"))
      (node (ref "D47") (pin "C") (pinfunction "C_C") (pintype "passive"))
      (node (ref "D62") (pin "C") (pinfunction "C_C") (pintype "passive"))
      (node (ref "_1") (pin "D0") (pinfunction "_D0_D0") (pintype "bidirectional"))
    )
    (net (code "4") (name "/COLUMN2") (class "Default")
      (node (ref "D18") (pin "C") (pinfunction "C_C") (pintype "passive"))
      (node (ref "D3") (pin "C") (pinfunction "C_C") (pintype "passive"))
      (node (ref "D33") (pin "C") (pinfunction "C_C") (pintype "passive"))
      (node (ref "D48") (pin "C") (pinfunction "C_C") (pintype "passive"))
      (node (ref "D63") (pin "C") (pinfunction "C_C") (pintype "passive"))
      (node (ref "_1") (pin "D1") (pinfunction "_D1_D1") (pintype "bidirectional"))
    )
    (net (code "5") (name "/COLUMN3") (class "Default")
      (node (ref "D19") (pin "C") (pinfunction "C_C") (pintype "passive"))
      (node (ref "D34") (pin "C") (pinfunction "C_C") (pintype "passive"))
      (node (ref "D4") (pin "C") (pinfunction "C_C") (pintype "passive"))
      (node (ref "D49") (pin "C") (pinfunction "C_C") (pintype "passive"))
      (node (ref "D64") (pin "C") (pinfunction "C_C") (pintype "passive"))
      (node (ref "_1") (pin "D2") (pinfunction "_D2_D2") (pintype "bidirectional"))
    )
    (net (code "6") (name "/COLUMN4") (class "Default")
      (node (ref "D20") (pin "C") (pinfunction "C_C") (pintype "passive"))
      (node (ref "D35") (pin "C") (pinfunction "C_C") (pintype "passive"))
      (node (ref "D5") (pin "C") (pinfunction "C_C") (pintype "passive"))
      (node (ref "D50") (pin "C") (pinfunction "C_C") (pintype "passive"))
      (node (ref "D65") (pin "C") (pinfunction "C_C") (pintype "passive"))
      (node (ref "_1") (pin "D3") (pinfunction "_D3_D3") (pintype "bidirectional"))
    )
    (net (code "7") (name "/COLUMN5") (class "Default")
      (node (ref "D21") (pin "C") (pinfunction "C_C") (pintype "passive"))
      (node (ref "D36") (pin "C") (pinfunction "C_C") (pintype "passive"))
      (node (ref "D51") (pin "C") (pinfunction "C_C") (pintype "passive"))
      (node (ref "D6") (pin "C") (pinfunction "C_C") (pintype "passive"))
      (node (ref "D66") (pin "C") (pinfunction "C_C") (pintype "passive"))
      (node (ref "_1") (pin "C6") (pinfunction "_C6_C6") (pintype "bidirectional"))
    )
    (net (code "8") (name "/COLUMN6") (class "Default")
      (node (ref "D22") (pin "C") (pinfunction "C_C") (pintype "passive"))
      (node (ref "D37") (pin "C") (pinfunction "C_C") (pintype "passive"))
      (node (ref "D52") (pin "C") (pinfunction "C_C") (pintype "passive"))
      (node (ref "D67") (pin "C") (pinfunction "C_C") (pintype "passive"))
      (node (ref "D7") (pin "C") (pinfunction "C_C") (pintype "passive"))
      (node (ref "_1") (pin "C7") (pinfunction "_C7_C7") (pintype "bidirectional"))
    )
    (net (code "9") (name "/COLUMN7") (class "Default")
      (node (ref "D23") (pin "C") (pinfunction "C_C") (pintype "passive"))
      (node (ref "D38") (pin "C") (pinfunction "C_C") (pintype "passive"))
      (node (ref "D53") (pin "C") (pinfunction "C_C") (pintype "passive"))
      (node (ref "D68") (pin "C") (pinfunction "C_C") (pintype "passive"))
      (node (ref "D8") (pin "C") (pinfunction "C_C") (pintype "passive"))
      (node (ref "_1") (pin "D5") (pinfunction "_D5_D5") (pintype "bidirectional"))
    )
    (net (code "10") (name "/COLUMN8") (class "Default")
      (node (ref "D24") (pin "C") (pinfunction "C_C") (pintype "passive"))
      (node (ref "D39") (pin "C") (pinfunction "C_C") (pintype "passive"))
      (node (ref "D54") (pin "C") (pinfunction "C_C") (pintype "passive"))
      (node (ref "D69") (pin "C") (pinfunction "C_C") (pintype "passive"))
      (node (ref "D9") (pin "C") (pinfunction "C_C") (pintype "passive"))
      (node (ref "_1") (pin "D4") (pinfunction "_D4_D4") (pintype "bidirectional"))
    )
    (net (code "11") (name "/COLUMN9") (class "Default")
      (node (ref "D10") (pin "C") (pinfunction "C_C") (pintype "passive"))
      (node (ref "D25") (pin "C") (pinfunction "C_C") (pintype "passive"))
      (node (ref "D40") (pin "C") (pinfunction "C_C") (pintype "passive"))
      (node (ref "D55") (pin "C") (pinfunction "C_C") (pintype "passive"))
      (node (ref "D70") (pin "C") (pinfunction "C_C") (pintype "passive"))
      (node (ref "_1") (pin "D6") (pinfunction "_D6_D6") (pintype "bidirectional"))
    )
    (net (code "12") (name "/COLUMN10") (class "Default")
      (node (ref "D11") (pin "C") (pinfunction "C_C") (pintype "passive"))
      (node (ref "D26") (pin "C") (pinfunction "C_C") (pintype "passive"))
      (node (ref "D41") (pin "C") (pinfunction "C_C") (pintype "passive"))
      (node (ref "D56") (pin "C") (pinfunction "C_C") (pintype "passive"))
      (node (ref "D71") (pin "C") (pinfunction "C_C") (pintype "passive"))
      (node (ref "_1") (pin "D7") (pinfunction "_D7_D7") (pintype "bidirectional"))
    )
    (net (code "13") (name "/COLUMN11") (class "Default")
      (node (ref "D12") (pin "C") (pinfunction "C_C") (pintype "passive"))
      (node (ref "D27") (pin "C") (pinfunction "C_C") (pintype "passive"))
      (node (ref "D42") (pin "C") (pinfunction "C_C") (pintype "passive"))
      (node (ref "D57") (pin "C") (pinfunction "C_C") (pintype "passive"))
      (node (ref "D72") (pin "C") (pinfunction "C_C") (pintype "passive"))
      (node (ref "_1") (pin "B4") (pinfunction "_B4_B4") (pintype "bidirectional"))
    )
    (net (code "14") (name "/COLUMN12") (class "Default")
      (node (ref "D13") (pin "C") (pinfunction "C_C") (pintype "passive"))
      (node (ref "D28") (pin "C") (pinfunction "C_C") (pintype "passive"))
      (node (ref "D43") (pin "C") (pinfunction "C_C") (pintype "passive"))
      (node (ref "D58") (pin "C") (pinfunction "C_C") (pintype "passive"))
      (node (ref "D73") (pin "C") (pinfunction "C_C") (pintype "passive"))
      (node (ref "_1") (pin "B5") (pinfunction "_B5_B5") (pintype "bidirectional"))
    )
    (net (code "15") (name "/COLUMN13") (class "Default")
      (node (ref "D14") (pin "C") (pinfunction "C_C") (pintype "passive"))
      (node (ref "D29") (pin "C") (pinfunction "C_C") (pintype "passive"))
      (node (ref "D44") (pin "C") (pinfunction "C_C") (pintype "passive"))
      (node (ref "D59") (pin "C") (pinfunction "C_C") (pintype "passive"))
      (node (ref "D74") (pin "C") (pinfunction "C_C") (pintype "passive"))
      (node (ref "_1") (pin "B6") (pinfunction "_B6_B6") (pintype "bidirectional"))
    )
    (net (code "16") (name "/COLUMN14") (class "Default")
      (node (ref "D15") (pin "C") (pinfunction "C_C") (pintype "passive"))
      (node (ref "D30") (pin "C") (pinfunction "C_C") (pintype "passive"))
      (node (ref "D45") (pin "C") (pinfunction "C_C") (pintype "passive"))
      (node (ref "D60") (pin "C") (pinfunction "C_C") (pintype "passive"))
      (node (ref "D75") (pin "C") (pinfunction "C_C") (pintype "passive"))
      (node (ref "_1") (pin "F7") (pinfunction "_F7_F7") (pintype "bidirectional"))
    )
    (net (code "17") (name "/GND") (class "Default")
      (node (ref "LED1") (pin "1") (pinfunction "VDD_1") (pintype "bidirectional"))
      (node (ref "LED10") (pin "1") (pinfunction "VDD_1") (pintype "bidirectional"))
      (node (ref "LED11") (pin "1") (pinfunction "VDD_1") (pintype "bidirectional"))
      (node (ref "LED12") (pin "1") (pinfunction "VDD_1") (pintype "bidirectional"))
      (node (ref "LED13") (pin "1") (pinfunction "VDD_1") (pintype "bidirectional"))
      (node (ref "LED14") (pin "1") (pinfunction "VDD_1") (pintype "bidirectional"))
      (node (ref "LED2") (pin "1") (pinfunction "VDD_1") (pintype "bidirectional"))
      (node (ref "LED3") (pin "1") (pinfunction "VDD_1") (pintype "bidirectional"))
      (node (ref "LED4") (pin "1") (pinfunction "VDD_1") (pintype "bidirectional"))
      (node (ref "LED5") (pin "1") (pinfunction "VDD_1") (pintype "bidirectional"))
      (node (ref "LED6") (pin "1") (pinfunction "VDD_1") (pintype "bidirectional"))
      (node (ref "LED7") (pin "1") (pinfunction "VDD_1") (pintype "bidirectional"))
      (node (ref "LED8") (pin "1") (pinfunction "VDD_1") (pintype "bidirectional"))
      (node (ref "LED9") (pin "1") (pinfunction "VDD_1") (pintype "bidirectional"))
      (node (ref "U$1") (pin "LED-") (pinfunction "LED-_LED-") (pintype "bidirectional"))
      (node (ref "U$10") (pin "LED-") (pinfunction "LED-_LED-") (pintype "bidirectional"))
      (node (ref "U$11") (pin "LED-") (pinfunction "LED-_LED-") (pintype "bidirectional"))
      (node (ref "U$12") (pin "LED-") (pinfunction "LED-_LED-") (pintype "bidirectional"))
      (node (ref "U$13") (pin "LED-") (pinfunction "LED-_LED-") (pintype "bidirectional"))
      (node (ref "U$14") (pin "LED-") (pinfunction "LED-_LED-") (pintype "bidirectional"))
      (node (ref "U$15") (pin "LED-") (pinfunction "LED-_LED-") (pintype "bidirectional"))
      (node (ref "U$16") (pin "LED-") (pinfunction "LED-_LED-") (pintype "bidirectional"))
      (node (ref "U$17") (pin "LED-") (pinfunction "LED-_LED-") (pintype "bidirectional"))
      (node (ref "U$18") (pin "LED-") (pinfunction "LED-_LED-") (pintype "bidirectional"))
      (node (ref "U$19") (pin "LED-") (pinfunction "LED-_LED-") (pintype "bidirectional"))
      (node (ref "U$2") (pin "LED-") (pinfunction "LED-_LED-") (pintype "bidirectional"))
      (node (ref "U$20") (pin "LED-") (pinfunction "LED-_LED-") (pintype "bidirectional"))
      (node (ref "U$21") (pin "LED-") (pinfunction "LED-_LED-") (pintype "bidirectional"))
      (node (ref "U$22") (pin "LED-") (pinfunction "LED-_LED-") (pintype "bidirectional"))
      (node (ref "U$23") (pin "LED-") (pinfunction "LED-_LED-") (pintype "bidirectional"))
      (node (ref "U$24") (pin "LED-") (pinfunction "LED-_LED-") (pintype "bidirectional"))
      (node (ref "U$25") (pin "LED-") (pinfunction "LED-_LED-") (pintype "bidirectional"))
      (node (ref "U$26") (pin "LED-") (pinfunction "LED-_LED-") (pintype "bidirectional"))
      (node (ref "U$27") (pin "LED-") (pinfunction "LED-_LED-") (pintype "bidirectional"))
      (node (ref "U$28") (pin "LED-") (pinfunction "LED-_LED-") (pintype "bidirectional"))
      (node (ref "U$29") (pin "LED-") (pinfunction "LED-_LED-") (pintype "bidirectional"))
      (node (ref "U$3") (pin "LED-") (pinfunction "LED-_LED-") (pintype "bidirectional"))
      (node (ref "U$30") (pin "LED-") (pinfunction "LED-_LED-") (pintype "bidirectional"))
      (node (ref "U$31") (pin "LED-") (pinfunction "LED-_LED-") (pintype "bidirectional"))
      (node (ref "U$32") (pin "LED-") (pinfunction "LED-_LED-") (pintype "bidirectional"))
      (node (ref "U$33") (pin "LED-") (pinfunction "LED-_LED-") (pintype "bidirectional"))
      (node (ref "U$34") (pin "LED-") (pinfunction "LED-_LED-") (pintype "bidirectional"))
      (node (ref "U$35") (pin "LED-") (pinfunction "LED-_LED-") (pintype "bidirectional"))
      (node (ref "U$36") (pin "LED-") (pinfunction "LED-_LED-") (pintype "bidirectional"))
      (node (ref "U$37") (pin "LED-") (pinfunction "LED-_LED-") (pintype "bidirectional"))
      (node (ref "U$38") (pin "LED-") (pinfunction "LED-_LED-") (pintype "bidirectional"))
      (node (ref "U$39") (pin "LED-") (pinfunction "LED-_LED-") (pintype "bidirectional"))
      (node (ref "U$4") (pin "LED-") (pinfunction "LED-_LED-") (pintype "bidirectional"))
      (node (ref "U$40") (pin "LED-") (pinfunction "LED-_LED-") (pintype "bidirectional"))
      (node (ref "U$41") (pin "LED-") (pinfunction "LED-_LED-") (pintype "bidirectional"))
      (node (ref "U$42") (pin "LED-") (pinfunction "LED-_LED-") (pintype "bidirectional"))
      (node (ref "U$43") (pin "LED-") (pinfunction "LED-_LED-") (pintype "bidirectional"))
      (node (ref "U$44") (pin "LED-") (pinfunction "LED-_LED-") (pintype "bidirectional"))
      (node (ref "U$45") (pin "LED-") (pinfunction "LED-_LED-") (pintype "bidirectional"))
      (node (ref "U$46") (pin "LED-") (pinfunction "LED-_LED-") (pintype "bidirectional"))
      (node (ref "U$47") (pin "LED-") (pinfunction "LED-_LED-") (pintype "bidirectional"))
      (node (ref "U$48") (pin "LED-") (pinfunction "LED-_LED-") (pintype "bidirectional"))
      (node (ref "U$49") (pin "LED-") (pinfunction "LED-_LED-") (pintype "bidirectional"))
      (node (ref "U$5") (pin "LED-") (pinfunction "LED-_LED-") (pintype "bidirectional"))
      (node (ref "U$50") (pin "LED-") (pinfunction "LED-_LED-") (pintype "bidirectional"))
      (node (ref "U$51") (pin "LED-") (pinfunction "LED-_LED-") (pintype "bidirectional"))
      (node (ref "U$52") (pin "LED-") (pinfunction "LED-_LED-") (pintype "bidirectional"))
      (node (ref "U$53") (pin "LED-") (pinfunction "LED-_LED-") (pintype "bidirectional"))
      (node (ref "U$54") (pin "LED-") (pinfunction "LED-_LED-") (pintype "bidirectional"))
      (node (ref "U$55") (pin "LED-") (pinfunction "LED-_LED-") (pintype "bidirectional"))
      (node (ref "U$56") (pin "LED-") (pinfunction "LED-_LED-") (pintype "bidirectional"))
      (node (ref "U$57") (pin "LED-") (pinfunction "LED-_LED-") (pintype "bidirectional"))
      (node (ref "U$58") (pin "LED-") (pinfunction "LED-_LED-") (pintype "bidirectional"))
      (node (ref "U$59") (pin "LED-") (pinfunction "LED-_LED-") (pintype "bidirectional"))
      (node (ref "U$6") (pin "LED-") (pinfunction "LED-_LED-") (pintype "bidirectional"))
      (node (ref "U$60") (pin "LED-") (pinfunction "LED-_LED-") (pintype "bidirectional"))
      (node (ref "U$61") (pin "LED-") (pinfunction "LED-_LED-") (pintype "bidirectional"))
      (node (ref "U$62") (pin "LED-") (pinfunction "LED-_LED-") (pintype "bidirectional"))
      (node (ref "U$63") (pin "LED-") (pinfunction "LED-_LED-") (pintype "bidirectional"))
      (node (ref "U$64") (pin "LED-") (pinfunction "LED-_LED-") (pintype "bidirectional"))
      (node (ref "U$65") (pin "LED-") (pinfunction "LED-_LED-") (pintype "bidirectional"))
      (node (ref "U$66") (pin "LED-") (pinfunction "LED-_LED-") (pintype "bidirectional"))
      (node (ref "U$67") (pin "LED-") (pinfunction "LED-_LED-") (pintype "bidirectional"))
      (node (ref "U$68") (pin "LED-") (pinfunction "LED-_LED-") (pintype "bidirectional"))
      (node (ref "U$69") (pin "LED-") (pinfunction "LED-_LED-") (pintype "bidirectional"))
      (node (ref "U$7") (pin "LED-") (pinfunction "LED-_LED-") (pintype "bidirectional"))
      (node (ref "U$70") (pin "LED-") (pinfunction "LED-_LED-") (pintype "bidirectional"))
      (node (ref "U$71") (pin "LED-") (pinfunction "LED-_LED-") (pintype "bidirectional"))
      (node (ref "U$72") (pin "LED-") (pinfunction "LED-_LED-") (pintype "bidirectional"))
      (node (ref "U$73") (pin "LED-") (pinfunction "LED-_LED-") (pintype "bidirectional"))
      (node (ref "U$74") (pin "LED-") (pinfunction "LED-_LED-") (pintype "bidirectional"))
      (node (ref "U$75") (pin "LED-") (pinfunction "LED-_LED-") (pintype "bidirectional"))
      (node (ref "U$8") (pin "LED-") (pinfunction "LED-_LED-") (pintype "bidirectional"))
      (node (ref "U$9") (pin "LED-") (pinfunction "LED-_LED-") (pintype "bidirectional"))
      (node (ref "_1") (pin "GND") (pinfunction "_GND_GND") (pintype "bidirectional"))
    )
    (net (code "18") (name "/LED+") (class "Default")
      (node (ref "U$1") (pin "LED+") (pinfunction "LED+_LED+") (pintype "bidirectional"))
      (node (ref "U$10") (pin "LED+") (pinfunction "LED+_LED+") (pintype "bidirectional"))
      (node (ref "U$11") (pin "LED+") (pinfunction "LED+_LED+") (pintype "bidirectional"))
      (node (ref "U$12") (pin "LED+") (pinfunction "LED+_LED+") (pintype "bidirectional"))
      (node (ref "U$13") (pin "LED+") (pinfunction "LED+_LED+") (pintype "bidirectional"))
      (node (ref "U$14") (pin "LED+") (pinfunction "LED+_LED+") (pintype "bidirectional"))
      (node (ref "U$15") (pin "LED+") (pinfunction "LED+_LED+") (pintype "bidirectional"))
      (node (ref "U$16") (pin "LED+") (pinfunction "LED+_LED+") (pintype "bidirectional"))
      (node (ref "U$17") (pin "LED+") (pinfunction "LED+_LED+") (pintype "bidirectional"))
      (node (ref "U$18") (pin "LED+") (pinfunction "LED+_LED+") (pintype "bidirectional"))
      (node (ref "U$19") (pin "LED+") (pinfunction "LED+_LED+") (pintype "bidirectional"))
      (node (ref "U$2") (pin "LED+") (pinfunction "LED+_LED+") (pintype "bidirectional"))
      (node (ref "U$20") (pin "LED+") (pinfunction "LED+_LED+") (pintype "bidirectional"))
      (node (ref "U$21") (pin "LED+") (pinfunction "LED+_LED+") (pintype "bidirectional"))
      (node (ref "U$22") (pin "LED+") (pinfunction "LED+_LED+") (pintype "bidirectional"))
      (node (ref "U$23") (pin "LED+") (pinfunction "LED+_LED+") (pintype "bidirectional"))
      (node (ref "U$24") (pin "LED+") (pinfunction "LED+_LED+") (pintype "bidirectional"))
      (node (ref "U$25") (pin "LED+") (pinfunction "LED+_LED+") (pintype "bidirectional"))
      (node (ref "U$26") (pin "LED+") (pinfunction "LED+_LED+") (pintype "bidirectional"))
      (node (ref "U$27") (pin "LED+") (pinfunction "LED+_LED+") (pintype "bidirectional"))
      (node (ref "U$28") (pin "LED+") (pinfunction "LED+_LED+") (pintype "bidirectional"))
      (node (ref "U$29") (pin "LED+") (pinfunction "LED+_LED+") (pintype "bidirectional"))
      (node (ref "U$3") (pin "LED+") (pinfunction "LED+_LED+") (pintype "bidirectional"))
      (node (ref "U$30") (pin "LED+") (pinfunction "LED+_LED+") (pintype "bidirectional"))
      (node (ref "U$31") (pin "LED+") (pinfunction "LED+_LED+") (pintype "bidirectional"))
      (node (ref "U$32") (pin "LED+") (pinfunction "LED+_LED+") (pintype "bidirectional"))
      (node (ref "U$33") (pin "LED+") (pinfunction "LED+_LED+") (pintype "bidirectional"))
      (node (ref "U$34") (pin "LED+") (pinfunction "LED+_LED+") (pintype "bidirectional"))
      (node (ref "U$35") (pin "LED+") (pinfunction "LED+_LED+") (pintype "bidirectional"))
      (node (ref "U$36") (pin "LED+") (pinfunction "LED+_LED+") (pintype "bidirectional"))
      (node (ref "U$37") (pin "LED+") (pinfunction "LED+_LED+") (pintype "bidirectional"))
      (node (ref "U$38") (pin "LED+") (pinfunction "LED+_LED+") (pintype "bidirectional"))
      (node (ref "U$39") (pin "LED+") (pinfunction "LED+_LED+") (pintype "bidirectional"))
      (node (ref "U$4") (pin "LED+") (pinfunction "LED+_LED+") (pintype "bidirectional"))
      (node (ref "U$40") (pin "LED+") (pinfunction "LED+_LED+") (pintype "bidirectional"))
      (node (ref "U$41") (pin "LED+") (pinfunction "LED+_LED+") (pintype "bidirectional"))
      (node (ref "U$42") (pin "LED+") (pinfunction "LED+_LED+") (pintype "bidirectional"))
      (node (ref "U$43") (pin "LED+") (pinfunction "LED+_LED+") (pintype "bidirectional"))
      (node (ref "U$44") (pin "LED+") (pinfunction "LED+_LED+") (pintype "bidirectional"))
      (node (ref "U$45") (pin "LED+") (pinfunction "LED+_LED+") (pintype "bidirectional"))
      (node (ref "U$46") (pin "LED+") (pinfunction "LED+_LED+") (pintype "bidirectional"))
      (node (ref "U$47") (pin "LED+") (pinfunction "LED+_LED+") (pintype "bidirectional"))
      (node (ref "U$48") (pin "LED+") (pinfunction "LED+_LED+") (pintype "bidirectional"))
      (node (ref "U$49") (pin "LED+") (pinfunction "LED+_LED+") (pintype "bidirectional"))
      (node (ref "U$5") (pin "LED+") (pinfunction "LED+_LED+") (pintype "bidirectional"))
      (node (ref "U$50") (pin "LED+") (pinfunction "LED+_LED+") (pintype "bidirectional"))
      (node (ref "U$51") (pin "LED+") (pinfunction "LED+_LED+") (pintype "bidirectional"))
      (node (ref "U$52") (pin "LED+") (pinfunction "LED+_LED+") (pintype "bidirectional"))
      (node (ref "U$53") (pin "LED+") (pinfunction "LED+_LED+") (pintype "bidirectional"))
      (node (ref "U$54") (pin "LED+") (pinfunction "LED+_LED+") (pintype "bidirectional"))
      (node (ref "U$55") (pin "LED+") (pinfunction "LED+_LED+") (pintype "bidirectional"))
      (node (ref "U$56") (pin "LED+") (pinfunction "LED+_LED+") (pintype "bidirectional"))
      (node (ref "U$57") (pin "LED+") (pinfunction "LED+_LED+") (pintype "bidirectional"))
      (node (ref "U$58") (pin "LED+") (pinfunction "LED+_LED+") (pintype "bidirectional"))
      (node (ref "U$59") (pin "LED+") (pinfunction "LED+_LED+") (pintype "bidirectional"))
      (node (ref "U$6") (pin "LED+") (pinfunction "LED+_LED+") (pintype "bidirectional"))
      (node (ref "U$60") (pin "LED+") (pinfunction "LED+_LED+") (pintype "bidirectional"))
      (node (ref "U$61") (pin "LED+") (pinfunction "LED+_LED+") (pintype "bidirectional"))
      (node (ref "U$62") (pin "LED+") (pinfunction "LED+_LED+") (pintype "bidirectional"))
      (node (ref "U$63") (pin "LED+") (pinfunction "LED+_LED+") (pintype "bidirectional"))
      (node (ref "U$64") (pin "LED+") (pinfunction "LED+_LED+") (pintype "bidirectional"))
      (node (ref "U$65") (pin "LED+") (pinfunction "LED+_LED+") (pintype "bidirectional"))
      (node (ref "U$66") (pin "LED+") (pinfunction "LED+_LED+") (pintype "bidirectional"))
      (node (ref "U$67") (pin "LED+") (pinfunction "LED+_LED+") (pintype "bidirectional"))
      (node (ref "U$68") (pin "LED+") (pinfunction "LED+_LED+") (pintype "bidirectional"))
      (node (ref "U$69") (pin "LED+") (pinfunction "LED+_LED+") (pintype "bidirectional"))
      (node (ref "U$7") (pin "LED+") (pinfunction "LED+_LED+") (pintype "bidirectional"))
      (node (ref "U$70") (pin "LED+") (pinfunction "LED+_LED+") (pintype "bidirectional"))
      (node (ref "U$71") (pin "LED+") (pinfunction "LED+_LED+") (pintype "bidirectional"))
      (node (ref "U$72") (pin "LED+") (pinfunction "LED+_LED+") (pintype "bidirectional"))
      (node (ref "U$73") (pin "LED+") (pinfunction "LED+_LED+") (pintype "bidirectional"))
      (node (ref "U$74") (pin "LED+") (pinfunction "LED+_LED+") (pintype "bidirectional"))
      (node (ref "U$75") (pin "LED+") (pinfunction "LED+_LED+") (pintype "bidirectional"))
      (node (ref "U$8") (pin "LED+") (pinfunction "LED+_LED+") (pintype "bidirectional"))
      (node (ref "U$9") (pin "LED+") (pinfunction "LED+_LED+") (pintype "bidirectional"))
    )
    (net (code "19") (name "/RGB_DATA") (class "Default")
      (node (ref "LED1") (pin "4") (pinfunction "DI_4") (pintype "bidirectional"))
      (node (ref "_1") (pin "F6") (pinfunction "_F6_F6") (pintype "bidirectional"))
    )
    (net (code "20") (name "/ROW0") (class "Default")
      (node (ref "U$1") (pin "UP") (pinfunction "UP_UP") (pintype "bidirectional"))
      (node (ref "U$10") (pin "UP") (pinfunction "UP_UP") (pintype "bidirectional"))
      (node (ref "U$11") (pin "UP") (pinfunction "UP_UP") (pintype "bidirectional"))
      (node (ref "U$12") (pin "UP") (pinfunction "UP_UP") (pintype "bidirectional"))
      (node (ref "U$13") (pin "UP") (pinfunction "UP_UP") (pintype "bidirectional"))
      (node (ref "U$14") (pin "UP") (pinfunction "UP_UP") (pintype "bidirectional"))
      (node (ref "U$15") (pin "UP") (pinfunction "UP_UP") (pintype "bidirectional"))
      (node (ref "U$2") (pin "UP") (pinfunction "UP_UP") (pintype "bidirectional"))
      (node (ref "U$3") (pin "UP") (pinfunction "UP_UP") (pintype "bidirectional"))
      (node (ref "U$4") (pin "UP") (pinfunction "UP_UP") (pintype "bidirectional"))
      (node (ref "U$5") (pin "UP") (pinfunction "UP_UP") (pintype "bidirectional"))
      (node (ref "U$6") (pin "UP") (pinfunction "UP_UP") (pintype "bidirectional"))
      (node (ref "U$7") (pin "UP") (pinfunction "UP_UP") (pintype "bidirectional"))
      (node (ref "U$8") (pin "UP") (pinfunction "UP_UP") (pintype "bidirectional"))
      (node (ref "U$9") (pin "UP") (pinfunction "UP_UP") (pintype "bidirectional"))
      (node (ref "_1") (pin "B0") (pinfunction "_B0_B0") (pintype "bidirectional"))
    )
    (net (code "21") (name "/ROW1") (class "Default")
      (node (ref "U$16") (pin "UP") (pinfunction "UP_UP") (pintype "bidirectional"))
      (node (ref "U$17") (pin "UP") (pinfunction "UP_UP") (pintype "bidirectional"))
      (node (ref "U$18") (pin "UP") (pinfunction "UP_UP") (pintype "bidirectional"))
      (node (ref "U$19") (pin "UP") (pinfunction "UP_UP") (pintype "bidirectional"))
      (node (ref "U$20") (pin "UP") (pinfunction "UP_UP") (pintype "bidirectional"))
      (node (ref "U$21") (pin "UP") (pinfunction "UP_UP") (pintype "bidirectional"))
      (node (ref "U$22") (pin "UP") (pinfunction "UP_UP") (pintype "bidirectional"))
      (node (ref "U$23") (pin "UP") (pinfunction "UP_UP") (pintype "bidirectional"))
      (node (ref "U$24") (pin "UP") (pinfunction "UP_UP") (pintype "bidirectional"))
      (node (ref "U$25") (pin "UP") (pinfunction "UP_UP") (pintype "bidirectional"))
      (node (ref "U$26") (pin "UP") (pinfunction "UP_UP") (pintype "bidirectional"))
      (node (ref "U$27") (pin "UP") (pinfunction "UP_UP") (pintype "bidirectional"))
      (node (ref "U$28") (pin "UP") (pinfunction "UP_UP") (pintype "bidirectional"))
      (node (ref "U$29") (pin "UP") (pinfunction "UP_UP") (pintype "bidirectional"))
      (node (ref "U$30") (pin "UP") (pinfunction "UP_UP") (pintype "bidirectional"))
      (node (ref "_1") (pin "B1") (pinfunction "_B1_B1") (pintype "bidirectional"))
    )
    (net (code "22") (name "/ROW2") (class "Default")
      (node (ref "U$31") (pin "UP") (pinfunction "UP_UP") (pintype "bidirectional"))
      (node (ref "U$32") (pin "UP") (pinfunction "UP_UP") (pintype "bidirectional"))
      (node (ref "U$33") (pin "UP") (pinfunction "UP_UP") (pintype "bidirectional"))
      (node (ref "U$34") (pin "UP") (pinfunction "UP_UP") (pintype "bidirectional"))
      (node (ref "U$35") (pin "UP") (pinfunction "UP_UP") (pintype "bidirectional"))
      (node (ref "U$36") (pin "UP") (pinfunction "UP_UP") (pintype "bidirectional"))
      (node (ref "U$37") (pin "UP") (pinfunction "UP_UP") (pintype "bidirectional"))
      (node (ref "U$38") (pin "UP") (pinfunction "UP_UP") (pintype "bidirectional"))
      (node (ref "U$39") (pin "UP") (pinfunction "UP_UP") (pintype "bidirectional"))
      (node (ref "U$40") (pin "UP") (pinfunction "UP_UP") (pintype "bidirectional"))
      (node (ref "U$41") (pin "UP") (pinfunction "UP_UP") (pintype "bidirectional"))
      (node (ref "U$42") (pin "UP") (pinfunction "UP_UP") (pintype "bidirectional"))
      (node (ref "U$43") (pin "UP") (pinfunction "UP_UP") (pintype "bidirectional"))
      (node (ref "U$44") (pin "UP") (pinfunction "UP_UP") (pintype "bidirectional"))
      (node (ref "U$45") (pin "UP") (pinfunction "UP_UP") (pintype "bidirectional"))
      (node (ref "_1") (pin "B2") (pinfunction "_B2_B2") (pintype "bidirectional"))
    )
    (net (code "23") (name "/ROW3") (class "Default")
      (node (ref "U$46") (pin "UP") (pinfunction "UP_UP") (pintype "bidirectional"))
      (node (ref "U$47") (pin "UP") (pinfunction "UP_UP") (pintype "bidirectional"))
      (node (ref "U$48") (pin "UP") (pinfunction "UP_UP") (pintype "bidirectional"))
      (node (ref "U$49") (pin "UP") (pinfunction "UP_UP") (pintype "bidirectional"))
      (node (ref "U$50") (pin "UP") (pinfunction "UP_UP") (pintype "bidirectional"))
      (node (ref "U$51") (pin "UP") (pinfunction "UP_UP") (pintype "bidirectional"))
      (node (ref "U$52") (pin "UP") (pinfunction "UP_UP") (pintype "bidirectional"))
      (node (ref "U$53") (pin "UP") (pinfunction "UP_UP") (pintype "bidirectional"))
      (node (ref "U$54") (pin "UP") (pinfunction "UP_UP") (pintype "bidirectional"))
      (node (ref "U$55") (pin "UP") (pinfunction "UP_UP") (pintype "bidirectional"))
      (node (ref "U$56") (pin "UP") (pinfunction "UP_UP") (pintype "bidirectional"))
      (node (ref "U$57") (pin "UP") (pinfunction "UP_UP") (pintype "bidirectional"))
      (node (ref "U$58") (pin "UP") (pinfunction "UP_UP") (pintype "bidirectional"))
      (node (ref "U$59") (pin "UP") (pinfunction "UP_UP") (pintype "bidirectional"))
      (node (ref "U$60") (pin "UP") (pinfunction "UP_UP") (pintype "bidirectional"))
      (node (ref "_1") (pin "B3") (pinfunction "_B3_B3") (pintype "bidirectional"))
    )
    (net (code "24") (name "/ROW4") (class "Default")
      (node (ref "U$61") (pin "UP") (pinfunction "UP_UP") (pintype "bidirectional"))
      (node (ref "U$62") (pin "UP") (pinfunction "UP_UP") (pintype "bidirectional"))
      (node (ref "U$63") (pin "UP") (pinfunction "UP_UP") (pintype "bidirectional"))
      (node (ref "U$64") (pin "UP") (pinfunction "UP_UP") (pintype "bidirectional"))
      (node (ref "U$65") (pin "UP") (pinfunction "UP_UP") (pintype "bidirectional"))
      (node (ref "U$66") (pin "UP") (pinfunction "UP_UP") (pintype "bidirectional"))
      (node (ref "U$67") (pin "UP") (pinfunction "UP_UP") (pintype "bidirectional"))
      (node (ref "U$68") (pin "UP") (pinfunction "UP_UP") (pintype "bidirectional"))
      (node (ref "U$69") (pin "UP") (pinfunction "UP_UP") (pintype "bidirectional"))
      (node (ref "U$70") (pin "UP") (pinfunction "UP_UP") (pintype "bidirectional"))
      (node (ref "U$71") (pin "UP") (pinfunction "UP_UP") (pintype "bidirectional"))
      (node (ref "U$72") (pin "UP") (pinfunction "UP_UP") (pintype "bidirectional"))
      (node (ref "U$73") (pin "UP") (pinfunction "UP_UP") (pintype "bidirectional"))
      (node (ref "U$74") (pin "UP") (pinfunction "UP_UP") (pintype "bidirectional"))
      (node (ref "U$75") (pin "UP") (pinfunction "UP_UP") (pintype "bidirectional"))
    )
    (net (code "25") (name "Net-(LED1-DO)") (class "Default")
      (node (ref "LED1") (pin "2") (pinfunction "DO_2") (pintype "bidirectional"))
      (node (ref "LED2") (pin "4") (pinfunction "DI_4") (pintype "bidirectional"))
    )
    (net (code "26") (name "Net-(LED2-DO)") (class "Default")
      (node (ref "LED2") (pin "2") (pinfunction "DO_2") (pintype "bidirectional"))
      (node (ref "LED3") (pin "4") (pinfunction "DI_4") (pintype "bidirectional"))
    )
    (net (code "27") (name "Net-(LED3-DO)") (class "Default")
      (node (ref "LED3") (pin "2") (pinfunction "DO_2") (pintype "bidirectional"))
      (node (ref "LED4") (pin "4") (pinfunction "DI_4") (pintype "bidirectional"))
    )
    (net (code "28") (name "Net-(LED4-DO)") (class "Default")
      (node (ref "LED4") (pin "2") (pinfunction "DO_2") (pintype "bidirectional"))
      (node (ref "LED5") (pin "4") (pinfunction "DI_4") (pintype "bidirectional"))
    )
    (net (code "29") (name "Net-(LED5-DO)") (class "Default")
      (node (ref "LED5") (pin "2") (pinfunction "DO_2") (pintype "bidirectional"))
      (node (ref "LED6") (pin "4") (pinfunction "DI_4") (pintype "bidirectional"))
    )
    (net (code "30") (name "Net-(LED6-DO)") (class "Default")
      (node (ref "LED6") (pin "2") (pinfunction "DO_2") (pintype "bidirectional"))
      (node (ref "LED7") (pin "4") (pinfunction "DI_4") (pintype "bidirectional"))
    )
    (net (code "31") (name "Net-(LED7-DO)") (class "Default")
      (node (ref "LED7") (pin "2") (pinfunction "DO_2") (pintype "bidirectional"))
      (node (ref "LED8") (pin "4") (pinfunction "DI_4") (pintype "bidirectional"))
    )
    (net (code "32") (name "Net-(LED8-DO)") (class "Default")
      (node (ref "LED8") (pin "2") (pinfunction "DO_2") (pintype "bidirectional"))
      (node (ref "LED9") (pin "4") (pinfunction "DI_4") (pintype "bidirectional"))
    )
    (net (code "33") (name "Net-(LED10-DI)") (class "Default")
      (node (ref "LED10") (pin "4") (pinfunction "DI_4") (pintype "bidirectional"))
      (node (ref "LED9") (pin "2") (pinfunction "DO_2") (pintype "bidirectional"))
    )
    (net (code "34") (name "Net-(LED10-DO)") (class "Default")
      (node (ref "LED10") (pin "2") (pinfunction "DO_2") (pintype "bidirectional"))
      (node (ref "LED11") (pin "4") (pinfunction "DI_4") (pintype "bidirectional"))
    )
    (net (code "35") (name "Net-(LED11-DO)") (class "Default")
      (node (ref "LED11") (pin "2") (pinfunction "DO_2") (pintype "bidirectional"))
      (node (ref "LED12") (pin "4") (pinfunction "DI_4") (pintype "bidirectional"))
    )
    (net (code "36") (name "Net-(LED12-DO)") (class "Default")
      (node (ref "LED12") (pin "2") (pinfunction "DO_2") (pintype "bidirectional"))
      (node (ref "LED13") (pin "4") (pinfunction "DI_4") (pintype "bidirectional"))
    )
    (net (code "37") (name "Net-(LED13-DO)") (class "Default")
      (node (ref "LED13") (pin "2") (pinfunction "DO_2") (pintype "bidirectional"))
      (node (ref "LED14") (pin "4") (pinfunction "DI_4") (pintype "bidirectional"))
    )
    (net (code "38") (name "Net-(U$1-A)") (class "Default")
      (node (ref "D1") (pin "A") (pinfunction "A_A") (pintype "passive"))
      (node (ref "U$1") (pin "SIDE") (pinfunction "A_SIDE") (pintype "bidirectional"))
    )
    (net (code "39") (name "Net-(U$2-A)") (class "Default")
      (node (ref "D2") (pin "A") (pinfunction "A_A") (pintype "passive"))
      (node (ref "U$2") (pin "SIDE") (pinfunction "A_SIDE") (pintype "bidirectional"))
    )
    (net (code "40") (name "Net-(U$3-A)") (class "Default")
      (node (ref "D3") (pin "A") (pinfunction "A_A") (pintype "passive"))
      (node (ref "U$3") (pin "SIDE") (pinfunction "A_SIDE") (pintype "bidirectional"))
    )
    (net (code "41") (name "Net-(U$4-A)") (class "Default")
      (node (ref "D4") (pin "A") (pinfunction "A_A") (pintype "passive"))
      (node (ref "U$4") (pin "SIDE") (pinfunction "A_SIDE") (pintype "bidirectional"))
    )
    (net (code "42") (name "Net-(U$5-A)") (class "Default")
      (node (ref "D5") (pin "A") (pinfunction "A_A") (pintype "passive"))
      (node (ref "U$5") (pin "SIDE") (pinfunction "A_SIDE") (pintype "bidirectional"))
    )
    (net (code "43") (name "Net-(U$6-A)") (class "Default")
      (node (ref "D6") (pin "A") (pinfunction "A_A") (pintype "passive"))
      (node (ref "U$6") (pin "SIDE") (pinfunction "A_SIDE") (pintype "bidirectional"))
    )
    (net (code "44") (name "Net-(U$7-A)") (class "Default")
      (node (ref "D7") (pin "A") (pinfunction "A_A") (pintype "passive"))
      (node (ref "U$7") (pin "SIDE") (pinfunction "A_SIDE") (pintype "bidirectional"))
    )
    (net (code "45") (name "Net-(U$8-A)") (class "Default")
      (node (ref "D8") (pin "A") (pinfunction "A_A") (pintype "passive"))
      (node (ref "U$8") (pin "SIDE") (pinfunction "A_SIDE") (pintype "bidirectional"))
    )
    (net (code "46") (name "Net-(U$9-A)") (class "Default")
      (node (ref "D9") (pin "A") (pinfunction "A_A") (pintype "passive"))
      (node (ref "U$9") (pin "SIDE") (pinfunction "A_SIDE") (pintype "bidirectional"))
    )
    (net (code "47") (name "Net-(U$10-A)") (class "Default")
      (node (ref "D10") (pin "A") (pinfunction "A_A") (pintype "passive"))
      (node (ref "U$10") (pin "SIDE") (pinfunction "A_SIDE") (pintype "bidirectional"))
    )
    (net (code "48") (name "Net-(U$11-A)") (class "Default")
      (node (ref "D11") (pin "A") (pinfunction "A_A") (pintype "passive"))
      (node (ref "U$11") (pin "SIDE") (pinfunction "A_SIDE") (pintype "bidirectional"))
    )
    (net (code "49") (name "Net-(U$12-A)") (class "Default")
      (node (ref "D12") (pin "A") (pinfunction "A_A") (pintype "passive"))
      (node (ref "U$12") (pin "SIDE") (pinfunction "A_SIDE") (pintype "bidirectional"))
    )
    (net (code "50") (name "Net-(U$13-A)") (class "Default")
      (node (ref "D13") (pin "A") (pinfunction "A_A") (pintype "passive"))
      (node (ref "U$13") (pin "SIDE") (pinfunction "A_SIDE") (pintype "bidirectional"))
    )
    (net (code "51") (name "Net-(U$14-A)") (class "Default")
      (node (ref "D14") (pin "A") (pinfunction "A_A") (pintype "passive"))
      (node (ref "U$14") (pin "SIDE") (pinfunction "A_SIDE") (pintype "bidirectional"))
    )
    (net (code "52") (name "Net-(U$15-A)") (class "Default")
      (node (ref "D15") (pin "A") (pinfunction "A_A") (pintype "passive"))
      (node (ref "U$15") (pin "SIDE") (pinfunction "A_SIDE") (pintype "bidirectional"))
    )
    (net (code "53") (name "Net-(U$16-A)") (class "Default")
      (node (ref "D16") (pin "A") (pinfunction "A_A") (pintype "passive"))
      (node (ref "U$16") (pin "SIDE") (pinfunction "A_SIDE") (pintype "bidirectional"))
    )
    (net (code "54") (name "Net-(U$17-A)") (class "Default")
      (node (ref "D17") (pin "A") (pinfunction "A_A") (pintype "passive"))
      (node (ref "U$17") (pin "SIDE") (pinfunction "A_SIDE") (pintype "bidirectional"))
    )
    (net (code "55") (name "Net-(U$18-A)") (class "Default")
      (node (ref "D18") (pin "A") (pinfunction "A_A") (pintype "passive"))
      (node (ref "U$18") (pin "SIDE") (pinfunction "A_SIDE") (pintype "bidirectional"))
    )
    (net (code "56") (name "Net-(U$19-A)") (class "Default")
      (node (ref "D19") (pin "A") (pinfunction "A_A") (pintype "passive"))
      (node (ref "U$19") (pin "SIDE") (pinfunction "A_SIDE") (pintype "bidirectional"))
    )
    (net (code "57") (name "Net-(U$20-A)") (class "Default")
      (node (ref "D20") (pin "A") (pinfunction "A_A") (pintype "passive"))
      (node (ref "U$20") (pin "SIDE") (pinfunction "A_SIDE") (pintype "bidirectional"))
    )
    (net (code "58") (name "Net-(U$21-A)") (class "Default")
      (node (ref "D21") (pin "A") (pinfunction "A_A") (pintype "passive"))
      (node (ref "U$21") (pin "SIDE") (pinfunction "A_SIDE") (pintype "bidirectional"))
    )
    (net (code "59") (name "Net-(U$22-A)") (class "Default")
      (node (ref "D22") (pin "A") (pinfunction "A_A") (pintype "passive"))
      (node (ref "U$22") (pin "SIDE") (pinfunction "A_SIDE") (pintype "bidirectional"))
    )
    (net (code "60") (name "Net-(U$23-A)") (class "Default")
      (node (ref "D23") (pin "A") (pinfunction "A_A") (pintype "passive"))
      (node (ref "U$23") (pin "SIDE") (pinfunction "A_SIDE") (pintype "bidirectional"))
    )
    (net (code "61") (name "Net-(U$24-A)") (class "Default")
      (node (ref "D24") (pin "A") (pinfunction "A_A") (pintype "passive"))
      (node (ref "U$24") (pin "SIDE") (pinfunction "A_SIDE") (pintype "bidirectional"))
    )
    (net (code "62") (name "Net-(U$25-A)") (class "Default")
      (node (ref "D25") (pin "A") (pinfunction "A_A") (pintype "passive"))
      (node (ref "U$25") (pin "SIDE") (pinfunction "A_SIDE") (pintype "bidirectional"))
    )
    (net (code "63") (name "Net-(U$26-A)") (class "Default")
      (node (ref "D26") (pin "A") (pinfunction "A_A") (pintype "passive"))
      (node (ref "U$26") (pin "SIDE") (pinfunction "A_SIDE") (pintype "bidirectional"))
    )
    (net (code "64") (name "Net-(U$27-A)") (class "Default")
      (node (ref "D27") (pin "A") (pinfunction "A_A") (pintype "passive"))
      (node (ref "U$27") (pin "SIDE") (pinfunction "A_SIDE") (pintype "bidirectional"))
    )
    (net (code "65") (name "Net-(U$28-A)") (class "Default")
      (node (ref "D28") (pin "A") (pinfunction "A_A") (pintype "passive"))
      (node (ref "U$28") (pin "SIDE") (pinfunction "A_SIDE") (pintype "bidirectional"))
    )
    (net (code "66") (name "Net-(U$29-A)") (class "Default")
      (node (ref "D29") (pin "A") (pinfunction "A_A") (pintype "passive"))
      (node (ref "U$29") (pin "SIDE") (pinfunction "A_SIDE") (pintype "bidirectional"))
    )
    (net (code "67") (name "Net-(U$30-A)") (class "Default")
      (node (ref "D30") (pin "A") (pinfunction "A_A") (pintype "passive"))
      (node (ref "U$30") (pin "SIDE") (pinfunction "A_SIDE") (pintype "bidirectional"))
    )
    (net (code "68") (name "Net-(U$31-A)") (class "Default")
      (node (ref "D31") (pin "A") (pinfunction "A_A") (pintype "passive"))
      (node (ref "U$31") (pin "SIDE") (pinfunction "A_SIDE") (pintype "bidirectional"))
    )
    (net (code "69") (name "Net-(U$32-A)") (class "Default")
      (node (ref "D32") (pin "A") (pinfunction "A_A") (pintype "passive"))
      (node (ref "U$32") (pin "SIDE") (pinfunction "A_SIDE") (pintype "bidirectional"))
    )
    (net (code "70") (name "Net-(U$33-A)") (class "Default")
      (node (ref "D33") (pin "A") (pinfunction "A_A") (pintype "passive"))
      (node (ref "U$33") (pin "SIDE") (pinfunction "A_SIDE") (pintype "bidirectional"))
    )
    (net (code "71") (name "Net-(U$34-A)") (class "Default")
      (node (ref "D34") (pin "A") (pinfunction "A_A") (pintype "passive"))
      (node (ref "U$34") (pin "SIDE") (pinfunction "A_SIDE") (pintype "bidirectional"))
    )
    (net (code "72") (name "Net-(U$35-A)") (class "Default")
      (node (ref "D35") (pin "A") (pinfunction "A_A") (pintype "passive"))
      (node (ref "U$35") (pin "SIDE") (pinfunction "A_SIDE") (pintype "bidirectional"))
    )
    (net (code "73") (name "Net-(U$36-A)") (class "Default")
      (node (ref "D36") (pin "A") (pinfunction "A_A") (pintype "passive"))
      (node (ref "U$36") (pin "SIDE") (pinfunction "A_SIDE") (pintype "bidirectional"))
    )
    (net (code "74") (name "Net-(U$37-A)") (class "Default")
      (node (ref "D37") (pin "A") (pinfunction "A_A") (pintype "passive"))
      (node (ref "U$37") (pin "SIDE") (pinfunction "A_SIDE") (pintype "bidirectional"))
    )
    (net (code "75") (name "Net-(U$38-A)") (class "Default")
      (node (ref "D38") (pin "A") (pinfunction "A_A") (pintype "passive"))
      (node (ref "U$38") (pin "SIDE") (pinfunction "A_SIDE") (pintype "bidirectional"))
    )
    (net (code "76") (name "Net-(U$39-A)") (class "Default")
      (node (ref "D39") (pin "A") (pinfunction "A_A") (pintype "passive"))
      (node (ref "U$39") (pin "SIDE") (pinfunction "A_SIDE") (pintype "bidirectional"))
    )
    (net (code "77") (name "Net-(U$40-A)") (class "Default")
      (node (ref "D40") (pin "A") (pinfunction "A_A") (pintype "passive"))
      (node (ref "U$40") (pin "SIDE") (pinfunction "A_SIDE") (pintype "bidirectional"))
    )
    (net (code "78") (name "Net-(U$41-A)") (class "Default")
      (node (ref "D41") (pin "A") (pinfunction "A_A") (pintype "passive"))
      (node (ref "U$41") (pin "SIDE") (pinfunction "A_SIDE") (pintype "bidirectional"))
    )
    (net (code "79") (name "Net-(U$42-A)") (class "Default")
      (node (ref "D42") (pin "A") (pinfunction "A_A") (pintype "passive"))
      (node (ref "U$42") (pin "SIDE") (pinfunction "A_SIDE") (pintype "bidirectional"))
    )
    (net (code "80") (name "Net-(U$43-A)") (class "Default")
      (node (ref "D43") (pin "A") (pinfunction "A_A") (pintype "passive"))
      (node (ref "U$43") (pin "SIDE") (pinfunction "A_SIDE") (pintype "bidirectional"))
    )
    (net (code "81") (name "Net-(U$44-A)") (class "Default")
      (node (ref "D44") (pin "A") (pinfunction "A_A") (pintype "passive"))
      (node (ref "U$44") (pin "SIDE") (pinfunction "A_SIDE") (pintype "bidirectional"))
    )
    (net (code "82") (name "Net-(U$45-A)") (class "Default")
      (node (ref "D45") (pin "A") (pinfunction "A_A") (pintype "passive"))
      (node (ref "U$45") (pin "SIDE") (pinfunction "A_SIDE") (pintype "bidirectional"))
    )
    (net (code "83") (name "Net-(U$46-A)") (class "Default")
      (node (ref "D46") (pin "A") (pinfunction "A_A") (pintype "passive"))
      (node (ref "U$46") (pin "SIDE") (pinfunction "A_SIDE") (pintype "bidirectional"))
    )
    (net (code "84") (name "Net-(U$47-A)") (class "Default")
      (node (ref "D47") (pin "A") (pinfunction "A_A") (pintype "passive"))
      (node (ref "U$47") (pin "SIDE") (pinfunction "A_SIDE") (pintype "bidirectional"))
    )
    (net (code "85") (name "Net-(U$48-A)") (class "Default")
      (node (ref "D48") (pin "A") (pinfunction "A_A") (pintype "passive"))
      (node (ref "U$48") (pin "SIDE") (pinfunction "A_SIDE") (pintype "bidirectional"))
    )
    (net (code "86") (name "Net-(U$49-A)") (class "Default")
      (node (ref "D49") (pin "A") (pinfunction "A_A") (pintype "passive"))
      (node (ref "U$49") (pin "SIDE") (pinfunction "A_SIDE") (pintype "bidirectional"))
    )
    (net (code "87") (name "Net-(U$50-A)") (class "Default")
      (node (ref "D50") (pin "A") (pinfunction "A_A") (pintype "passive"))
      (node (ref "U$50") (pin "SIDE") (pinfunction "A_SIDE") (pintype "bidirectional"))
    )
    (net (code "88") (name "Net-(U$51-A)") (class "Default")
      (node (ref "D51") (pin "A") (pinfunction "A_A") (pintype "passive"))
      (node (ref "U$51") (pin "SIDE") (pinfunction "A_SIDE") (pintype "bidirectional"))
    )
    (net (code "89") (name "Net-(U$52-A)") (class "Default")
      (node (ref "D52") (pin "A") (pinfunction "A_A") (pintype "passive"))
      (node (ref "U$52") (pin "SIDE") (pinfunction "A_SIDE") (pintype "bidirectional"))
    )
    (net (code "90") (name "Net-(U$53-A)") (class "Default")
      (node (ref "D53") (pin "A") (pinfunction "A_A") (pintype "passive"))
      (node (ref "U$53") (pin "SIDE") (pinfunction "A_SIDE") (pintype "bidirectional"))
    )
    (net (code "91") (name "Net-(U$54-A)") (class "Default")
      (node (ref "D54") (pin "A") (pinfunction "A_A") (pintype "passive"))
      (node (ref "U$54") (pin "SIDE") (pinfunction "A_SIDE") (pintype "bidirectional"))
    )
    (net (code "92") (name "Net-(U$55-A)") (class "Default")
      (node (ref "D55") (pin "A") (pinfunction "A_A") (pintype "passive"))
      (node (ref "U$55") (pin "SIDE") (pinfunction "A_SIDE") (pintype "bidirectional"))
    )
    (net (code "93") (name "Net-(U$56-A)") (class "Default")
      (node (ref "D56") (pin "A") (pinfunction "A_A") (pintype "passive"))
      (node (ref "U$56") (pin "SIDE") (pinfunction "A_SIDE") (pintype "bidirectional"))
    )
    (net (code "94") (name "Net-(U$57-A)") (class "Default")
      (node (ref "D57") (pin "A") (pinfunction "A_A") (pintype "passive"))
      (node (ref "U$57") (pin "SIDE") (pinfunction "A_SIDE") (pintype "bidirectional"))
    )
    (net (code "95") (name "Net-(U$58-A)") (class "Default")
      (node (ref "D58") (pin "A") (pinfunction "A_A") (pintype "passive"))
      (node (ref "U$58") (pin "SIDE") (pinfunction "A_SIDE") (pintype "bidirectional"))
    )
    (net (code "96") (name "Net-(U$59-A)") (class "Default")
      (node (ref "D59") (pin "A") (pinfunction "A_A") (pintype "passive"))
      (node (ref "U$59") (pin "SIDE") (pinfunction "A_SIDE") (pintype "bidirectional"))
    )
    (net (code "97") (name "Net-(U$60-A)") (class "Default")
      (node (ref "D60") (pin "A") (pinfunction "A_A") (pintype "passive"))
      (node (ref "U$60") (pin "SIDE") (pinfunction "A_SIDE") (pintype "bidirectional"))
    )
    (net (code "98") (name "Net-(U$61-A)") (class "Default")
      (node (ref "D61") (pin "A") (pinfunction "A_A") (pintype "passive"))
      (node (ref "U$61") (pin "SIDE") (pinfunction "A_SIDE") (pintype "bidirectional"))
    )
    (net (code "99") (name "Net-(U$62-A)") (class "Default")
      (node (ref "D62") (pin "A") (pinfunction "A_A") (pintype "passive"))
      (node (ref "U$62") (pin "SIDE") (pinfunction "A_SIDE") (pintype "bidirectional"))
    )
    (net (code "100") (name "Net-(U$63-A)") (class "Default")
      (node (ref "D63") (pin "A") (pinfunction "A_A") (pintype "passive"))
      (node (ref "U$63") (pin "SIDE") (pinfunction "A_SIDE") (pintype "bidirectional"))
    )
    (net (code "101") (name "Net-(U$64-A)") (class "Default")
      (node (ref "D64") (pin "A") (pinfunction "A_A") (pintype "passive"))
      (node (ref "U$64") (pin "SIDE") (pinfunction "A_SIDE") (pintype "bidirectional"))
    )
    (net (code "102") (name "Net-(U$65-A)") (class "Default")
      (node (ref "D65") (pin "A") (pinfunction "A_A") (pintype "passive"))
      (node (ref "U$65") (pin "SIDE") (pinfunction "A_SIDE") (pintype "bidirectional"))
    )
    (net (code "103") (name "Net-(U$66-A)") (class "Default")
      (node (ref "D66") (pin "A") (pinfunction "A_A") (pintype "passive"))
      (node (ref "U$66") (pin "SIDE") (pinfunction "A_SIDE") (pintype "bidirectional"))
    )
    (net (code "104") (name "Net-(U$67-A)") (class "Default")
      (node (ref "D67") (pin "A") (pinfunction "A_A") (pintype "passive"))
      (node (ref "U$67") (pin "SIDE") (pinfunction "A_SIDE") (pintype "bidirectional"))
    )
    (net (code "105") (name "Net-(U$68-A)") (class "Default")
      (node (ref "D68") (pin "A") (pinfunction "A_A") (pintype "passive"))
      (node (ref "U$68") (pin "SIDE") (pinfunction "A_SIDE") (pintype "bidirectional"))
    )
    (net (code "106") (name "Net-(U$69-A)") (class "Default")
      (node (ref "D69") (pin "A") (pinfunction "A_A") (pintype "passive"))
      (node (ref "U$69") (pin "SIDE") (pinfunction "A_SIDE") (pintype "bidirectional"))
    )
    (net (code "107") (name "Net-(U$70-A)") (class "Default")
      (node (ref "D70") (pin "A") (pinfunction "A_A") (pintype "passive"))
      (node (ref "U$70") (pin "SIDE") (pinfunction "A_SIDE") (pintype "bidirectional"))
    )
    (net (code "108") (name "Net-(U$71-A)") (class "Default")
      (node (ref "D71") (pin "A") (pinfunction "A_A") (pintype "passive"))
      (node (ref "U$71") (pin "SIDE") (pinfunction "A_SIDE") (pintype "bidirectional"))
    )
    (net (code "109") (name "Net-(U$72-A)") (class "Default")
      (node (ref "D72") (pin "A") (pinfunction "A_A") (pintype "passive"))
      (node (ref "U$72") (pin "SIDE") (pinfunction "A_SIDE") (pintype "bidirectional"))
    )
    (net (code "110") (name "Net-(U$73-A)") (class "Default")
      (node (ref "D73") (pin "A") (pinfunction "A_A") (pintype "passive"))
      (node (ref "U$73") (pin "SIDE") (pinfunction "A_SIDE") (pintype "bidirectional"))
    )
    (net (code "111") (name "Net-(U$74-A)") (class "Default")
      (node (ref "D74") (pin "A") (pinfunction "A_A") (pintype "passive"))
      (node (ref "U$74") (pin "SIDE") (pinfunction "A_SIDE") (pintype "bidirectional"))
    )
    (net (code "112") (name "Net-(U$75-A)") (class "Default")
      (node (ref "D75") (pin "A") (pinfunction "A_A") (pintype "passive"))
      (node (ref "U$75") (pin "SIDE") (pinfunction "A_SIDE") (pintype "bidirectional"))
    )
    (net (code "113") (name "unconnected-(LED14-DO-Pad2)") (class "Default")
      (node (ref "LED14") (pin "2") (pinfunction "DO_2") (pintype "bidirectional"))
    )
    (net (code "114") (name "unconnected-(_1-_5V2-Pad5V2)") (class "Default")
      (node (ref "_1") (pin "5V2") (pinfunction "_5V2_5V2") (pintype "bidirectional"))
    )
    (net (code "115") (name "unconnected-(_1-_E6-PadE6)") (class "Default")
      (node (ref "_1") (pin "E6") (pinfunction "_E6_E6") (pintype "bidirectional"))
    )
    (net (code "116") (name "unconnected-(_1-_F0-PadF0)") (class "Default")
      (node (ref "_1") (pin "F0") (pinfunction "_F0_F0") (pintype "bidirectional"))
    )
    (net (code "117") (name "unconnected-(_1-_F1-PadF1)") (class "Default")
      (node (ref "_1") (pin "F1") (pinfunction "_F1_F1") (pintype "bidirectional"))
    )
    (net (code "118") (name "unconnected-(_1-_F4-PadF4)") (class "Default")
      (node (ref "_1") (pin "F4") (pinfunction "_F4_F4") (pintype "bidirectional"))
    )
    (net (code "119") (name "unconnected-(_1-_F5-PadF5)") (class "Default")
      (node (ref "_1") (pin "F5") (pinfunction "_F5_F5") (pintype "bidirectional"))
    )
    (net (code "120") (name "unconnected-(_1-_GND1-PadGRND1)") (class "Default")
      (node (ref "_1") (pin "GRND1") (pinfunction "_GND1_GRND1") (pintype "bidirectional"))
    )
    (net (code "121") (name "unconnected-(_1-_REF-PadREF)") (class "Default")
      (node (ref "_1") (pin "REF") (pinfunction "_REF_REF") (pintype "bidirectional"))
    )
    (net (code "122") (name "unconnected-(_1-_RST-PadRST)") (class "Default")
      (node (ref "_1") (pin "RST") (pinfunction "_RST_RST") (pintype "bidirectional"))
    )
  )
)
